# array_4x4.net
KiCad netlist of a schematic drawn in EAGLE
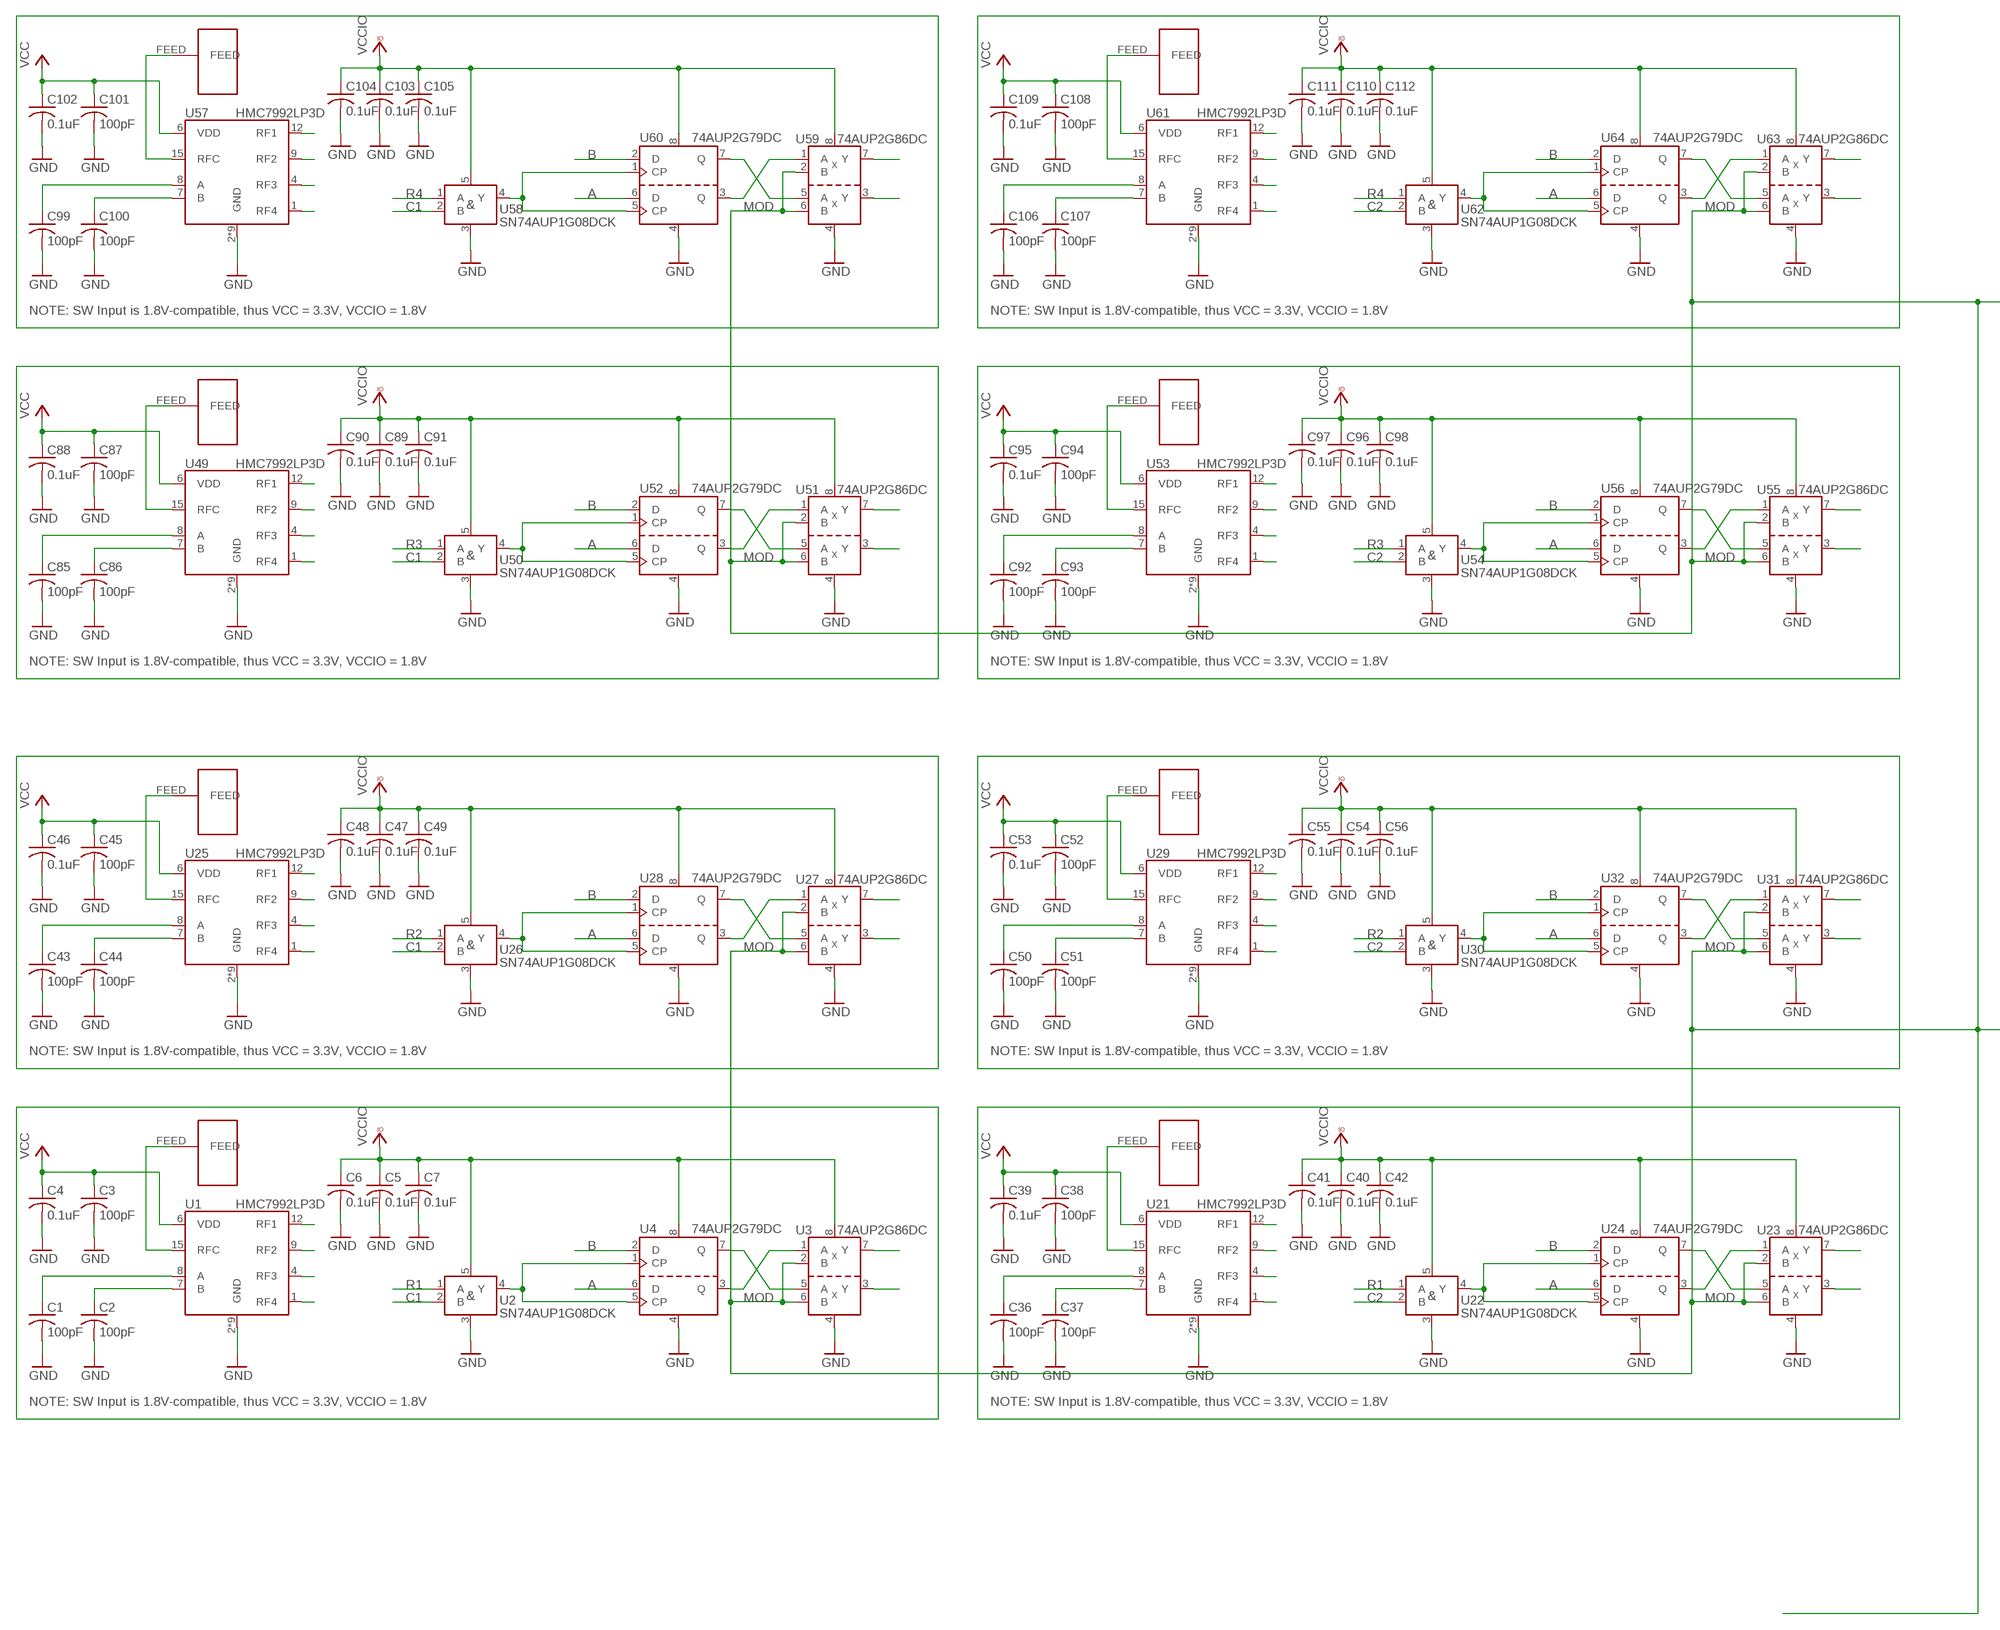
[diagram p0: schematic, sheet 1, part 1 of 2]
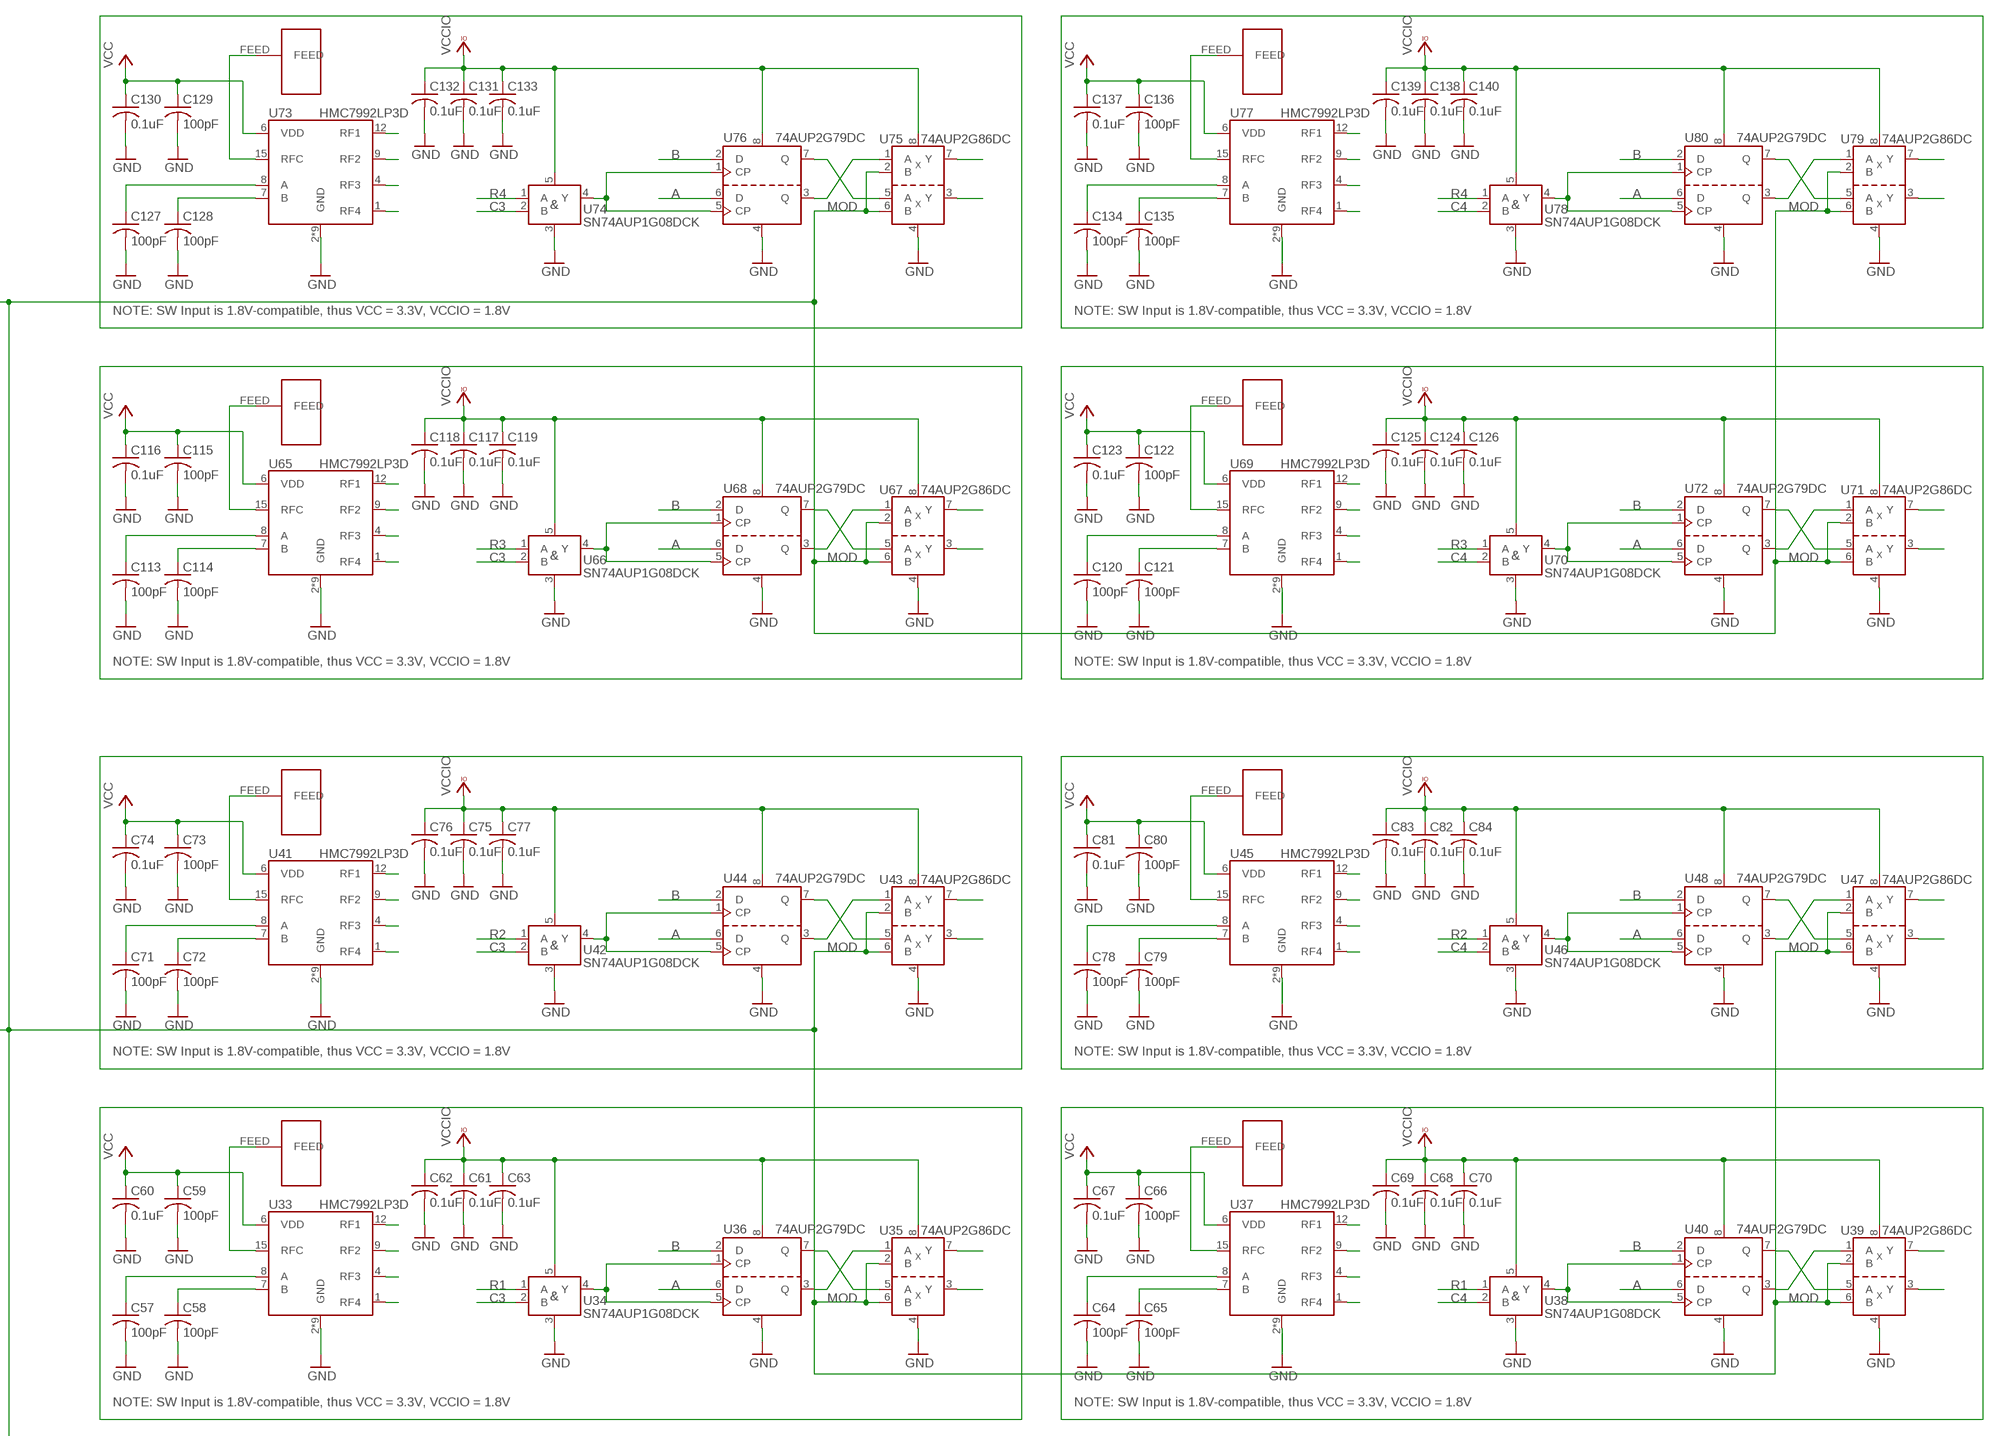
[diagram p1: schematic, sheet 1, part 2 of 2]

(export (version "E")
  (design (tool "Eeschema 10.0.6"))
  (components
    (comp (ref "ANT1")
      (value "5GANTENNA")
      (footprint "eagle-import:5GANTENNA")
      (libsource (lib "eagle-import") (part "5GANTENNA"))
    )
    (comp (ref "ANT6")
      (value "5GANTENNA")
      (footprint "eagle-import:5GANTENNA")
      (libsource (lib "eagle-import") (part "5GANTENNA"))
    )
    (comp (ref "ANT7")
      (value "5GANTENNA")
      (footprint "eagle-import:5GANTENNA")
      (libsource (lib "eagle-import") (part "5GANTENNA"))
    )
    (comp (ref "ANT8")
      (value "5GANTENNA")
      (footprint "eagle-import:5GANTENNA")
      (libsource (lib "eagle-import") (part "5GANTENNA"))
    )
    (comp (ref "ANT9")
      (value "5GANTENNA")
      (footprint "eagle-import:5GANTENNA")
      (libsource (lib "eagle-import") (part "5GANTENNA"))
    )
    (comp (ref "ANT10")
      (value "5GANTENNA")
      (footprint "eagle-import:5GANTENNA")
      (libsource (lib "eagle-import") (part "5GANTENNA"))
    )
    (comp (ref "ANT11")
      (value "5GANTENNA")
      (footprint "eagle-import:5GANTENNA")
      (libsource (lib "eagle-import") (part "5GANTENNA"))
    )
    (comp (ref "ANT12")
      (value "5GANTENNA")
      (footprint "eagle-import:5GANTENNA")
      (libsource (lib "eagle-import") (part "5GANTENNA"))
    )
    (comp (ref "ANT13")
      (value "5GANTENNA")
      (footprint "eagle-import:5GANTENNA")
      (libsource (lib "eagle-import") (part "5GANTENNA"))
    )
    (comp (ref "ANT14")
      (value "5GANTENNA")
      (footprint "eagle-import:5GANTENNA")
      (libsource (lib "eagle-import") (part "5GANTENNA"))
    )
    (comp (ref "ANT15")
      (value "5GANTENNA")
      (footprint "eagle-import:5GANTENNA")
      (libsource (lib "eagle-import") (part "5GANTENNA"))
    )
    (comp (ref "ANT16")
      (value "5GANTENNA")
      (footprint "eagle-import:5GANTENNA")
      (libsource (lib "eagle-import") (part "5GANTENNA"))
    )
    (comp (ref "ANT17")
      (value "5GANTENNA")
      (footprint "eagle-import:5GANTENNA")
      (libsource (lib "eagle-import") (part "5GANTENNA"))
    )
    (comp (ref "ANT18")
      (value "5GANTENNA")
      (footprint "eagle-import:5GANTENNA")
      (libsource (lib "eagle-import") (part "5GANTENNA"))
    )
    (comp (ref "ANT19")
      (value "5GANTENNA")
      (footprint "eagle-import:5GANTENNA")
      (libsource (lib "eagle-import") (part "5GANTENNA"))
    )
    (comp (ref "ANT20")
      (value "5GANTENNA")
      (footprint "eagle-import:5GANTENNA")
      (libsource (lib "eagle-import") (part "5GANTENNA"))
    )
    (comp (ref "C1")
      (value "100pF")
      (footprint "eagle-import:C0402")
      (libsource (lib "eagle-import") (part "C-USC0402"))
    )
    (comp (ref "C2")
      (value "100pF")
      (footprint "eagle-import:C0402")
      (libsource (lib "eagle-import") (part "C-USC0402"))
    )
    (comp (ref "C3")
      (value "100pF")
      (footprint "eagle-import:C0402")
      (libsource (lib "eagle-import") (part "C-USC0402"))
    )
    (comp (ref "C4")
      (value "0.1uF")
      (footprint "eagle-import:C0402")
      (libsource (lib "eagle-import") (part "C-USC0402"))
    )
    (comp (ref "C5")
      (value "0.1uF")
      (footprint "eagle-import:C0402")
      (libsource (lib "eagle-import") (part "C-USC0402"))
    )
    (comp (ref "C6")
      (value "0.1uF")
      (footprint "eagle-import:C0402")
      (libsource (lib "eagle-import") (part "C-USC0402"))
    )
    (comp (ref "C7")
      (value "0.1uF")
      (footprint "eagle-import:C0402")
      (libsource (lib "eagle-import") (part "C-USC0402"))
    )
    (comp (ref "C36")
      (value "100pF")
      (footprint "eagle-import:C0402")
      (libsource (lib "eagle-import") (part "C-USC0402"))
    )
    (comp (ref "C37")
      (value "100pF")
      (footprint "eagle-import:C0402")
      (libsource (lib "eagle-import") (part "C-USC0402"))
    )
    (comp (ref "C38")
      (value "100pF")
      (footprint "eagle-import:C0402")
      (libsource (lib "eagle-import") (part "C-USC0402"))
    )
    (comp (ref "C39")
      (value "0.1uF")
      (footprint "eagle-import:C0402")
      (libsource (lib "eagle-import") (part "C-USC0402"))
    )
    (comp (ref "C40")
      (value "0.1uF")
      (footprint "eagle-import:C0402")
      (libsource (lib "eagle-import") (part "C-USC0402"))
    )
    (comp (ref "C41")
      (value "0.1uF")
      (footprint "eagle-import:C0402")
      (libsource (lib "eagle-import") (part "C-USC0402"))
    )
    (comp (ref "C42")
      (value "0.1uF")
      (footprint "eagle-import:C0402")
      (libsource (lib "eagle-import") (part "C-USC0402"))
    )
    (comp (ref "C43")
      (value "100pF")
      (footprint "eagle-import:C0402")
      (libsource (lib "eagle-import") (part "C-USC0402"))
    )
    (comp (ref "C44")
      (value "100pF")
      (footprint "eagle-import:C0402")
      (libsource (lib "eagle-import") (part "C-USC0402"))
    )
    (comp (ref "C45")
      (value "100pF")
      (footprint "eagle-import:C0402")
      (libsource (lib "eagle-import") (part "C-USC0402"))
    )
    (comp (ref "C46")
      (value "0.1uF")
      (footprint "eagle-import:C0402")
      (libsource (lib "eagle-import") (part "C-USC0402"))
    )
    (comp (ref "C47")
      (value "0.1uF")
      (footprint "eagle-import:C0402")
      (libsource (lib "eagle-import") (part "C-USC0402"))
    )
    (comp (ref "C48")
      (value "0.1uF")
      (footprint "eagle-import:C0402")
      (libsource (lib "eagle-import") (part "C-USC0402"))
    )
    (comp (ref "C49")
      (value "0.1uF")
      (footprint "eagle-import:C0402")
      (libsource (lib "eagle-import") (part "C-USC0402"))
    )
    (comp (ref "C50")
      (value "100pF")
      (footprint "eagle-import:C0402")
      (libsource (lib "eagle-import") (part "C-USC0402"))
    )
    (comp (ref "C51")
      (value "100pF")
      (footprint "eagle-import:C0402")
      (libsource (lib "eagle-import") (part "C-USC0402"))
    )
    (comp (ref "C52")
      (value "100pF")
      (footprint "eagle-import:C0402")
      (libsource (lib "eagle-import") (part "C-USC0402"))
    )
    (comp (ref "C53")
      (value "0.1uF")
      (footprint "eagle-import:C0402")
      (libsource (lib "eagle-import") (part "C-USC0402"))
    )
    (comp (ref "C54")
      (value "0.1uF")
      (footprint "eagle-import:C0402")
      (libsource (lib "eagle-import") (part "C-USC0402"))
    )
    (comp (ref "C55")
      (value "0.1uF")
      (footprint "eagle-import:C0402")
      (libsource (lib "eagle-import") (part "C-USC0402"))
    )
    (comp (ref "C56")
      (value "0.1uF")
      (footprint "eagle-import:C0402")
      (libsource (lib "eagle-import") (part "C-USC0402"))
    )
    (comp (ref "C57")
      (value "100pF")
      (footprint "eagle-import:C0402")
      (libsource (lib "eagle-import") (part "C-USC0402"))
    )
    (comp (ref "C58")
      (value "100pF")
      (footprint "eagle-import:C0402")
      (libsource (lib "eagle-import") (part "C-USC0402"))
    )
    (comp (ref "C59")
      (value "100pF")
      (footprint "eagle-import:C0402")
      (libsource (lib "eagle-import") (part "C-USC0402"))
    )
    (comp (ref "C60")
      (value "0.1uF")
      (footprint "eagle-import:C0402")
      (libsource (lib "eagle-import") (part "C-USC0402"))
    )
    (comp (ref "C61")
      (value "0.1uF")
      (footprint "eagle-import:C0402")
      (libsource (lib "eagle-import") (part "C-USC0402"))
    )
    (comp (ref "C62")
      (value "0.1uF")
      (footprint "eagle-import:C0402")
      (libsource (lib "eagle-import") (part "C-USC0402"))
    )
    (comp (ref "C63")
      (value "0.1uF")
      (footprint "eagle-import:C0402")
      (libsource (lib "eagle-import") (part "C-USC0402"))
    )
    (comp (ref "C64")
      (value "100pF")
      (footprint "eagle-import:C0402")
      (libsource (lib "eagle-import") (part "C-USC0402"))
    )
    (comp (ref "C65")
      (value "100pF")
      (footprint "eagle-import:C0402")
      (libsource (lib "eagle-import") (part "C-USC0402"))
    )
    (comp (ref "C66")
      (value "100pF")
      (footprint "eagle-import:C0402")
      (libsource (lib "eagle-import") (part "C-USC0402"))
    )
    (comp (ref "C67")
      (value "0.1uF")
      (footprint "eagle-import:C0402")
      (libsource (lib "eagle-import") (part "C-USC0402"))
    )
    (comp (ref "C68")
      (value "0.1uF")
      (footprint "eagle-import:C0402")
      (libsource (lib "eagle-import") (part "C-USC0402"))
    )
    (comp (ref "C69")
      (value "0.1uF")
      (footprint "eagle-import:C0402")
      (libsource (lib "eagle-import") (part "C-USC0402"))
    )
    (comp (ref "C70")
      (value "0.1uF")
      (footprint "eagle-import:C0402")
      (libsource (lib "eagle-import") (part "C-USC0402"))
    )
    (comp (ref "C71")
      (value "100pF")
      (footprint "eagle-import:C0402")
      (libsource (lib "eagle-import") (part "C-USC0402"))
    )
    (comp (ref "C72")
      (value "100pF")
      (footprint "eagle-import:C0402")
      (libsource (lib "eagle-import") (part "C-USC0402"))
    )
    (comp (ref "C73")
      (value "100pF")
      (footprint "eagle-import:C0402")
      (libsource (lib "eagle-import") (part "C-USC0402"))
    )
    (comp (ref "C74")
      (value "0.1uF")
      (footprint "eagle-import:C0402")
      (libsource (lib "eagle-import") (part "C-USC0402"))
    )
    (comp (ref "C75")
      (value "0.1uF")
      (footprint "eagle-import:C0402")
      (libsource (lib "eagle-import") (part "C-USC0402"))
    )
    (comp (ref "C76")
      (value "0.1uF")
      (footprint "eagle-import:C0402")
      (libsource (lib "eagle-import") (part "C-USC0402"))
    )
    (comp (ref "C77")
      (value "0.1uF")
      (footprint "eagle-import:C0402")
      (libsource (lib "eagle-import") (part "C-USC0402"))
    )
    (comp (ref "C78")
      (value "100pF")
      (footprint "eagle-import:C0402")
      (libsource (lib "eagle-import") (part "C-USC0402"))
    )
    (comp (ref "C79")
      (value "100pF")
      (footprint "eagle-import:C0402")
      (libsource (lib "eagle-import") (part "C-USC0402"))
    )
    (comp (ref "C80")
      (value "100pF")
      (footprint "eagle-import:C0402")
      (libsource (lib "eagle-import") (part "C-USC0402"))
    )
    (comp (ref "C81")
      (value "0.1uF")
      (footprint "eagle-import:C0402")
      (libsource (lib "eagle-import") (part "C-USC0402"))
    )
    (comp (ref "C82")
      (value "0.1uF")
      (footprint "eagle-import:C0402")
      (libsource (lib "eagle-import") (part "C-USC0402"))
    )
    (comp (ref "C83")
      (value "0.1uF")
      (footprint "eagle-import:C0402")
      (libsource (lib "eagle-import") (part "C-USC0402"))
    )
    (comp (ref "C84")
      (value "0.1uF")
      (footprint "eagle-import:C0402")
      (libsource (lib "eagle-import") (part "C-USC0402"))
    )
    (comp (ref "C85")
      (value "100pF")
      (footprint "eagle-import:C0402")
      (libsource (lib "eagle-import") (part "C-USC0402"))
    )
    (comp (ref "C86")
      (value "100pF")
      (footprint "eagle-import:C0402")
      (libsource (lib "eagle-import") (part "C-USC0402"))
    )
    (comp (ref "C87")
      (value "100pF")
      (footprint "eagle-import:C0402")
      (libsource (lib "eagle-import") (part "C-USC0402"))
    )
    (comp (ref "C88")
      (value "0.1uF")
      (footprint "eagle-import:C0402")
      (libsource (lib "eagle-import") (part "C-USC0402"))
    )
    (comp (ref "C89")
      (value "0.1uF")
      (footprint "eagle-import:C0402")
      (libsource (lib "eagle-import") (part "C-USC0402"))
    )
    (comp (ref "C90")
      (value "0.1uF")
      (footprint "eagle-import:C0402")
      (libsource (lib "eagle-import") (part "C-USC0402"))
    )
    (comp (ref "C91")
      (value "0.1uF")
      (footprint "eagle-import:C0402")
      (libsource (lib "eagle-import") (part "C-USC0402"))
    )
    (comp (ref "C92")
      (value "100pF")
      (footprint "eagle-import:C0402")
      (libsource (lib "eagle-import") (part "C-USC0402"))
    )
    (comp (ref "C93")
      (value "100pF")
      (footprint "eagle-import:C0402")
      (libsource (lib "eagle-import") (part "C-USC0402"))
    )
    (comp (ref "C94")
      (value "100pF")
      (footprint "eagle-import:C0402")
      (libsource (lib "eagle-import") (part "C-USC0402"))
    )
    (comp (ref "C95")
      (value "0.1uF")
      (footprint "eagle-import:C0402")
      (libsource (lib "eagle-import") (part "C-USC0402"))
    )
    (comp (ref "C96")
      (value "0.1uF")
      (footprint "eagle-import:C0402")
      (libsource (lib "eagle-import") (part "C-USC0402"))
    )
    (comp (ref "C97")
      (value "0.1uF")
      (footprint "eagle-import:C0402")
      (libsource (lib "eagle-import") (part "C-USC0402"))
    )
    (comp (ref "C98")
      (value "0.1uF")
      (footprint "eagle-import:C0402")
      (libsource (lib "eagle-import") (part "C-USC0402"))
    )
    (comp (ref "C99")
      (value "100pF")
      (footprint "eagle-import:C0402")
      (libsource (lib "eagle-import") (part "C-USC0402"))
    )
    (comp (ref "C100")
      (value "100pF")
      (footprint "eagle-import:C0402")
      (libsource (lib "eagle-import") (part "C-USC0402"))
    )
    (comp (ref "C101")
      (value "100pF")
      (footprint "eagle-import:C0402")
      (libsource (lib "eagle-import") (part "C-USC0402"))
    )
    (comp (ref "C102")
      (value "0.1uF")
      (footprint "eagle-import:C0402")
      (libsource (lib "eagle-import") (part "C-USC0402"))
    )
    (comp (ref "C103")
      (value "0.1uF")
      (footprint "eagle-import:C0402")
      (libsource (lib "eagle-import") (part "C-USC0402"))
    )
    (comp (ref "C104")
      (value "0.1uF")
      (footprint "eagle-import:C0402")
      (libsource (lib "eagle-import") (part "C-USC0402"))
    )
    (comp (ref "C105")
      (value "0.1uF")
      (footprint "eagle-import:C0402")
      (libsource (lib "eagle-import") (part "C-USC0402"))
    )
    (comp (ref "C106")
      (value "100pF")
      (footprint "eagle-import:C0402")
      (libsource (lib "eagle-import") (part "C-USC0402"))
    )
    (comp (ref "C107")
      (value "100pF")
      (footprint "eagle-import:C0402")
      (libsource (lib "eagle-import") (part "C-USC0402"))
    )
    (comp (ref "C108")
      (value "100pF")
      (footprint "eagle-import:C0402")
      (libsource (lib "eagle-import") (part "C-USC0402"))
    )
    (comp (ref "C109")
      (value "0.1uF")
      (footprint "eagle-import:C0402")
      (libsource (lib "eagle-import") (part "C-USC0402"))
    )
    (comp (ref "C110")
      (value "0.1uF")
      (footprint "eagle-import:C0402")
      (libsource (lib "eagle-import") (part "C-USC0402"))
    )
    (comp (ref "C111")
      (value "0.1uF")
      (footprint "eagle-import:C0402")
      (libsource (lib "eagle-import") (part "C-USC0402"))
    )
    (comp (ref "C112")
      (value "0.1uF")
      (footprint "eagle-import:C0402")
      (libsource (lib "eagle-import") (part "C-USC0402"))
    )
    (comp (ref "C113")
      (value "100pF")
      (footprint "eagle-import:C0402")
      (libsource (lib "eagle-import") (part "C-USC0402"))
    )
    (comp (ref "C114")
      (value "100pF")
      (footprint "eagle-import:C0402")
      (libsource (lib "eagle-import") (part "C-USC0402"))
    )
    (comp (ref "C115")
      (value "100pF")
      (footprint "eagle-import:C0402")
      (libsource (lib "eagle-import") (part "C-USC0402"))
    )
    (comp (ref "C116")
      (value "0.1uF")
      (footprint "eagle-import:C0402")
      (libsource (lib "eagle-import") (part "C-USC0402"))
    )
    (comp (ref "C117")
      (value "0.1uF")
      (footprint "eagle-import:C0402")
      (libsource (lib "eagle-import") (part "C-USC0402"))
    )
    (comp (ref "C118")
      (value "0.1uF")
      (footprint "eagle-import:C0402")
      (libsource (lib "eagle-import") (part "C-USC0402"))
    )
    (comp (ref "C119")
      (value "0.1uF")
      (footprint "eagle-import:C0402")
      (libsource (lib "eagle-import") (part "C-USC0402"))
    )
    (comp (ref "C120")
      (value "100pF")
      (footprint "eagle-import:C0402")
      (libsource (lib "eagle-import") (part "C-USC0402"))
    )
    (comp (ref "C121")
      (value "100pF")
      (footprint "eagle-import:C0402")
      (libsource (lib "eagle-import") (part "C-USC0402"))
    )
    (comp (ref "C122")
      (value "100pF")
      (footprint "eagle-import:C0402")
      (libsource (lib "eagle-import") (part "C-USC0402"))
    )
    (comp (ref "C123")
      (value "0.1uF")
      (footprint "eagle-import:C0402")
      (libsource (lib "eagle-import") (part "C-USC0402"))
    )
    (comp (ref "C124")
      (value "0.1uF")
      (footprint "eagle-import:C0402")
      (libsource (lib "eagle-import") (part "C-USC0402"))
    )
    (comp (ref "C125")
      (value "0.1uF")
      (footprint "eagle-import:C0402")
      (libsource (lib "eagle-import") (part "C-USC0402"))
    )
    (comp (ref "C126")
      (value "0.1uF")
      (footprint "eagle-import:C0402")
      (libsource (lib "eagle-import") (part "C-USC0402"))
    )
    (comp (ref "C127")
      (value "100pF")
      (footprint "eagle-import:C0402")
      (libsource (lib "eagle-import") (part "C-USC0402"))
    )
    (comp (ref "C128")
      (value "100pF")
      (footprint "eagle-import:C0402")
      (libsource (lib "eagle-import") (part "C-USC0402"))
    )
    (comp (ref "C129")
      (value "100pF")
      (footprint "eagle-import:C0402")
      (libsource (lib "eagle-import") (part "C-USC0402"))
    )
    (comp (ref "C130")
      (value "0.1uF")
      (footprint "eagle-import:C0402")
      (libsource (lib "eagle-import") (part "C-USC0402"))
    )
    (comp (ref "C131")
      (value "0.1uF")
      (footprint "eagle-import:C0402")
      (libsource (lib "eagle-import") (part "C-USC0402"))
    )
    (comp (ref "C132")
      (value "0.1uF")
      (footprint "eagle-import:C0402")
      (libsource (lib "eagle-import") (part "C-USC0402"))
    )
    (comp (ref "C133")
      (value "0.1uF")
      (footprint "eagle-import:C0402")
      (libsource (lib "eagle-import") (part "C-USC0402"))
    )
    (comp (ref "C134")
      (value "100pF")
      (footprint "eagle-import:C0402")
      (libsource (lib "eagle-import") (part "C-USC0402"))
    )
    (comp (ref "C135")
      (value "100pF")
      (footprint "eagle-import:C0402")
      (libsource (lib "eagle-import") (part "C-USC0402"))
    )
    (comp (ref "C136")
      (value "100pF")
      (footprint "eagle-import:C0402")
      (libsource (lib "eagle-import") (part "C-USC0402"))
    )
    (comp (ref "C137")
      (value "0.1uF")
      (footprint "eagle-import:C0402")
      (libsource (lib "eagle-import") (part "C-USC0402"))
    )
    (comp (ref "C138")
      (value "0.1uF")
      (footprint "eagle-import:C0402")
      (libsource (lib "eagle-import") (part "C-USC0402"))
    )
    (comp (ref "C139")
      (value "0.1uF")
      (footprint "eagle-import:C0402")
      (libsource (lib "eagle-import") (part "C-USC0402"))
    )
    (comp (ref "C140")
      (value "0.1uF")
      (footprint "eagle-import:C0402")
      (libsource (lib "eagle-import") (part "C-USC0402"))
    )
    (comp (ref "U1")
      (value "HMC7992LP3D")
      (footprint "eagle-import:QFN-16-3X3")
      (libsource (lib "eagle-import") (part "HMC7992LP3D"))
    )
    (comp (ref "U2")
      (value "SN74AUP1G08DCK")
      (footprint "eagle-import:SOT-353")
      (libsource (lib "eagle-import") (part "SN74AUP1G08DCK"))
    )
    (comp (ref "U3")
      (value "74AUP2G86DC")
      (footprint "eagle-import:VSSOP-8")
      (libsource (lib "eagle-import") (part "74AUP2G86DC"))
    )
    (comp (ref "U4")
      (value "74AUP2G79DC")
      (footprint "eagle-import:VSSOP-8")
      (libsource (lib "eagle-import") (part "74AUP2G79DC"))
    )
    (comp (ref "U21")
      (value "HMC7992LP3D")
      (footprint "eagle-import:QFN-16-3X3")
      (libsource (lib "eagle-import") (part "HMC7992LP3D"))
    )
    (comp (ref "U22")
      (value "SN74AUP1G08DCK")
      (footprint "eagle-import:SOT-353")
      (libsource (lib "eagle-import") (part "SN74AUP1G08DCK"))
    )
    (comp (ref "U23")
      (value "74AUP2G86DC")
      (footprint "eagle-import:VSSOP-8")
      (libsource (lib "eagle-import") (part "74AUP2G86DC"))
    )
    (comp (ref "U24")
      (value "74AUP2G79DC")
      (footprint "eagle-import:VSSOP-8")
      (libsource (lib "eagle-import") (part "74AUP2G79DC"))
    )
    (comp (ref "U25")
      (value "HMC7992LP3D")
      (footprint "eagle-import:QFN-16-3X3")
      (libsource (lib "eagle-import") (part "HMC7992LP3D"))
    )
    (comp (ref "U26")
      (value "SN74AUP1G08DCK")
      (footprint "eagle-import:SOT-353")
      (libsource (lib "eagle-import") (part "SN74AUP1G08DCK"))
    )
    (comp (ref "U27")
      (value "74AUP2G86DC")
      (footprint "eagle-import:VSSOP-8")
      (libsource (lib "eagle-import") (part "74AUP2G86DC"))
    )
    (comp (ref "U28")
      (value "74AUP2G79DC")
      (footprint "eagle-import:VSSOP-8")
      (libsource (lib "eagle-import") (part "74AUP2G79DC"))
    )
    (comp (ref "U29")
      (value "HMC7992LP3D")
      (footprint "eagle-import:QFN-16-3X3")
      (libsource (lib "eagle-import") (part "HMC7992LP3D"))
    )
    (comp (ref "U30")
      (value "SN74AUP1G08DCK")
      (footprint "eagle-import:SOT-353")
      (libsource (lib "eagle-import") (part "SN74AUP1G08DCK"))
    )
    (comp (ref "U31")
      (value "74AUP2G86DC")
      (footprint "eagle-import:VSSOP-8")
      (libsource (lib "eagle-import") (part "74AUP2G86DC"))
    )
    (comp (ref "U32")
      (value "74AUP2G79DC")
      (footprint "eagle-import:VSSOP-8")
      (libsource (lib "eagle-import") (part "74AUP2G79DC"))
    )
    (comp (ref "U33")
      (value "HMC7992LP3D")
      (footprint "eagle-import:QFN-16-3X3")
      (libsource (lib "eagle-import") (part "HMC7992LP3D"))
    )
    (comp (ref "U34")
      (value "SN74AUP1G08DCK")
      (footprint "eagle-import:SOT-353")
      (libsource (lib "eagle-import") (part "SN74AUP1G08DCK"))
    )
    (comp (ref "U35")
      (value "74AUP2G86DC")
      (footprint "eagle-import:VSSOP-8")
      (libsource (lib "eagle-import") (part "74AUP2G86DC"))
    )
    (comp (ref "U36")
      (value "74AUP2G79DC")
      (footprint "eagle-import:VSSOP-8")
      (libsource (lib "eagle-import") (part "74AUP2G79DC"))
    )
    (comp (ref "U37")
      (value "HMC7992LP3D")
      (footprint "eagle-import:QFN-16-3X3")
      (libsource (lib "eagle-import") (part "HMC7992LP3D"))
    )
    (comp (ref "U38")
      (value "SN74AUP1G08DCK")
      (footprint "eagle-import:SOT-353")
      (libsource (lib "eagle-import") (part "SN74AUP1G08DCK"))
    )
    (comp (ref "U39")
      (value "74AUP2G86DC")
      (footprint "eagle-import:VSSOP-8")
      (libsource (lib "eagle-import") (part "74AUP2G86DC"))
    )
    (comp (ref "U40")
      (value "74AUP2G79DC")
      (footprint "eagle-import:VSSOP-8")
      (libsource (lib "eagle-import") (part "74AUP2G79DC"))
    )
    (comp (ref "U41")
      (value "HMC7992LP3D")
      (footprint "eagle-import:QFN-16-3X3")
      (libsource (lib "eagle-import") (part "HMC7992LP3D"))
    )
    (comp (ref "U42")
      (value "SN74AUP1G08DCK")
      (footprint "eagle-import:SOT-353")
      (libsource (lib "eagle-import") (part "SN74AUP1G08DCK"))
    )
    (comp (ref "U43")
      (value "74AUP2G86DC")
      (footprint "eagle-import:VSSOP-8")
      (libsource (lib "eagle-import") (part "74AUP2G86DC"))
    )
    (comp (ref "U44")
      (value "74AUP2G79DC")
      (footprint "eagle-import:VSSOP-8")
      (libsource (lib "eagle-import") (part "74AUP2G79DC"))
    )
    (comp (ref "U45")
      (value "HMC7992LP3D")
      (footprint "eagle-import:QFN-16-3X3")
      (libsource (lib "eagle-import") (part "HMC7992LP3D"))
    )
    (comp (ref "U46")
      (value "SN74AUP1G08DCK")
      (footprint "eagle-import:SOT-353")
      (libsource (lib "eagle-import") (part "SN74AUP1G08DCK"))
    )
    (comp (ref "U47")
      (value "74AUP2G86DC")
      (footprint "eagle-import:VSSOP-8")
      (libsource (lib "eagle-import") (part "74AUP2G86DC"))
    )
    (comp (ref "U48")
      (value "74AUP2G79DC")
      (footprint "eagle-import:VSSOP-8")
      (libsource (lib "eagle-import") (part "74AUP2G79DC"))
    )
    (comp (ref "U49")
      (value "HMC7992LP3D")
      (footprint "eagle-import:QFN-16-3X3")
      (libsource (lib "eagle-import") (part "HMC7992LP3D"))
    )
    (comp (ref "U50")
      (value "SN74AUP1G08DCK")
      (footprint "eagle-import:SOT-353")
      (libsource (lib "eagle-import") (part "SN74AUP1G08DCK"))
    )
    (comp (ref "U51")
      (value "74AUP2G86DC")
      (footprint "eagle-import:VSSOP-8")
      (libsource (lib "eagle-import") (part "74AUP2G86DC"))
    )
    (comp (ref "U52")
      (value "74AUP2G79DC")
      (footprint "eagle-import:VSSOP-8")
      (libsource (lib "eagle-import") (part "74AUP2G79DC"))
    )
    (comp (ref "U53")
      (value "HMC7992LP3D")
      (footprint "eagle-import:QFN-16-3X3")
      (libsource (lib "eagle-import") (part "HMC7992LP3D"))
    )
    (comp (ref "U54")
      (value "SN74AUP1G08DCK")
      (footprint "eagle-import:SOT-353")
      (libsource (lib "eagle-import") (part "SN74AUP1G08DCK"))
    )
    (comp (ref "U55")
      (value "74AUP2G86DC")
      (footprint "eagle-import:VSSOP-8")
      (libsource (lib "eagle-import") (part "74AUP2G86DC"))
    )
    (comp (ref "U56")
      (value "74AUP2G79DC")
      (footprint "eagle-import:VSSOP-8")
      (libsource (lib "eagle-import") (part "74AUP2G79DC"))
    )
    (comp (ref "U57")
      (value "HMC7992LP3D")
      (footprint "eagle-import:QFN-16-3X3")
      (libsource (lib "eagle-import") (part "HMC7992LP3D"))
    )
    (comp (ref "U58")
      (value "SN74AUP1G08DCK")
      (footprint "eagle-import:SOT-353")
      (libsource (lib "eagle-import") (part "SN74AUP1G08DCK"))
    )
    (comp (ref "U59")
      (value "74AUP2G86DC")
      (footprint "eagle-import:VSSOP-8")
      (libsource (lib "eagle-import") (part "74AUP2G86DC"))
    )
    (comp (ref "U60")
      (value "74AUP2G79DC")
      (footprint "eagle-import:VSSOP-8")
      (libsource (lib "eagle-import") (part "74AUP2G79DC"))
    )
    (comp (ref "U61")
      (value "HMC7992LP3D")
      (footprint "eagle-import:QFN-16-3X3")
      (libsource (lib "eagle-import") (part "HMC7992LP3D"))
    )
    (comp (ref "U62")
      (value "SN74AUP1G08DCK")
      (footprint "eagle-import:SOT-353")
      (libsource (lib "eagle-import") (part "SN74AUP1G08DCK"))
    )
    (comp (ref "U63")
      (value "74AUP2G86DC")
      (footprint "eagle-import:VSSOP-8")
      (libsource (lib "eagle-import") (part "74AUP2G86DC"))
    )
    (comp (ref "U64")
      (value "74AUP2G79DC")
      (footprint "eagle-import:VSSOP-8")
      (libsource (lib "eagle-import") (part "74AUP2G79DC"))
    )
    (comp (ref "U65")
      (value "HMC7992LP3D")
      (footprint "eagle-import:QFN-16-3X3")
      (libsource (lib "eagle-import") (part "HMC7992LP3D"))
    )
    (comp (ref "U66")
      (value "SN74AUP1G08DCK")
      (footprint "eagle-import:SOT-353")
      (libsource (lib "eagle-import") (part "SN74AUP1G08DCK"))
    )
    (comp (ref "U67")
      (value "74AUP2G86DC")
      (footprint "eagle-import:VSSOP-8")
      (libsource (lib "eagle-import") (part "74AUP2G86DC"))
    )
    (comp (ref "U68")
      (value "74AUP2G79DC")
      (footprint "eagle-import:VSSOP-8")
      (libsource (lib "eagle-import") (part "74AUP2G79DC"))
    )
    (comp (ref "U69")
      (value "HMC7992LP3D")
      (footprint "eagle-import:QFN-16-3X3")
      (libsource (lib "eagle-import") (part "HMC7992LP3D"))
    )
    (comp (ref "U70")
      (value "SN74AUP1G08DCK")
      (footprint "eagle-import:SOT-353")
      (libsource (lib "eagle-import") (part "SN74AUP1G08DCK"))
    )
    (comp (ref "U71")
      (value "74AUP2G86DC")
      (footprint "eagle-import:VSSOP-8")
      (libsource (lib "eagle-import") (part "74AUP2G86DC"))
    )
    (comp (ref "U72")
      (value "74AUP2G79DC")
      (footprint "eagle-import:VSSOP-8")
      (libsource (lib "eagle-import") (part "74AUP2G79DC"))
    )
    (comp (ref "U73")
      (value "HMC7992LP3D")
      (footprint "eagle-import:QFN-16-3X3")
      (libsource (lib "eagle-import") (part "HMC7992LP3D"))
    )
    (comp (ref "U74")
      (value "SN74AUP1G08DCK")
      (footprint "eagle-import:SOT-353")
      (libsource (lib "eagle-import") (part "SN74AUP1G08DCK"))
    )
    (comp (ref "U75")
      (value "74AUP2G86DC")
      (footprint "eagle-import:VSSOP-8")
      (libsource (lib "eagle-import") (part "74AUP2G86DC"))
    )
    (comp (ref "U76")
      (value "74AUP2G79DC")
      (footprint "eagle-import:VSSOP-8")
      (libsource (lib "eagle-import") (part "74AUP2G79DC"))
    )
    (comp (ref "U77")
      (value "HMC7992LP3D")
      (footprint "eagle-import:QFN-16-3X3")
      (libsource (lib "eagle-import") (part "HMC7992LP3D"))
    )
    (comp (ref "U78")
      (value "SN74AUP1G08DCK")
      (footprint "eagle-import:SOT-353")
      (libsource (lib "eagle-import") (part "SN74AUP1G08DCK"))
    )
    (comp (ref "U79")
      (value "74AUP2G86DC")
      (footprint "eagle-import:VSSOP-8")
      (libsource (lib "eagle-import") (part "74AUP2G86DC"))
    )
    (comp (ref "U80")
      (value "74AUP2G79DC")
      (footprint "eagle-import:VSSOP-8")
      (libsource (lib "eagle-import") (part "74AUP2G79DC"))
    )
  )
  (nets
    (net (code "1") (name "/A") (class "Default")
      (node (ref "U24") (pin "6") (pinfunction "D_6") (pintype "input"))
      (node (ref "U28") (pin "6") (pinfunction "D_6") (pintype "input"))
      (node (ref "U32") (pin "6") (pinfunction "D_6") (pintype "input"))
      (node (ref "U36") (pin "6") (pinfunction "D_6") (pintype "input"))
      (node (ref "U4") (pin "6") (pinfunction "D_6") (pintype "input"))
      (node (ref "U40") (pin "6") (pinfunction "D_6") (pintype "input"))
      (node (ref "U44") (pin "6") (pinfunction "D_6") (pintype "input"))
      (node (ref "U48") (pin "6") (pinfunction "D_6") (pintype "input"))
      (node (ref "U52") (pin "6") (pinfunction "D_6") (pintype "input"))
      (node (ref "U56") (pin "6") (pinfunction "D_6") (pintype "input"))
      (node (ref "U60") (pin "6") (pinfunction "D_6") (pintype "input"))
      (node (ref "U64") (pin "6") (pinfunction "D_6") (pintype "input"))
      (node (ref "U68") (pin "6") (pinfunction "D_6") (pintype "input"))
      (node (ref "U72") (pin "6") (pinfunction "D_6") (pintype "input"))
      (node (ref "U76") (pin "6") (pinfunction "D_6") (pintype "input"))
      (node (ref "U80") (pin "6") (pinfunction "D_6") (pintype "input"))
    )
    (net (code "2") (name "/B") (class "Default")
      (node (ref "U24") (pin "2") (pinfunction "D_2") (pintype "input"))
      (node (ref "U28") (pin "2") (pinfunction "D_2") (pintype "input"))
      (node (ref "U32") (pin "2") (pinfunction "D_2") (pintype "input"))
      (node (ref "U36") (pin "2") (pinfunction "D_2") (pintype "input"))
      (node (ref "U4") (pin "2") (pinfunction "D_2") (pintype "input"))
      (node (ref "U40") (pin "2") (pinfunction "D_2") (pintype "input"))
      (node (ref "U44") (pin "2") (pinfunction "D_2") (pintype "input"))
      (node (ref "U48") (pin "2") (pinfunction "D_2") (pintype "input"))
      (node (ref "U52") (pin "2") (pinfunction "D_2") (pintype "input"))
      (node (ref "U56") (pin "2") (pinfunction "D_2") (pintype "input"))
      (node (ref "U60") (pin "2") (pinfunction "D_2") (pintype "input"))
      (node (ref "U64") (pin "2") (pinfunction "D_2") (pintype "input"))
      (node (ref "U68") (pin "2") (pinfunction "D_2") (pintype "input"))
      (node (ref "U72") (pin "2") (pinfunction "D_2") (pintype "input"))
      (node (ref "U76") (pin "2") (pinfunction "D_2") (pintype "input"))
      (node (ref "U80") (pin "2") (pinfunction "D_2") (pintype "input"))
    )
    (net (code "3") (name "/C1") (class "Default")
      (node (ref "U2") (pin "2") (pinfunction "B_2") (pintype "input"))
      (node (ref "U26") (pin "2") (pinfunction "B_2") (pintype "input"))
      (node (ref "U50") (pin "2") (pinfunction "B_2") (pintype "input"))
      (node (ref "U58") (pin "2") (pinfunction "B_2") (pintype "input"))
    )
    (net (code "4") (name "/C2") (class "Default")
      (node (ref "U22") (pin "2") (pinfunction "B_2") (pintype "input"))
      (node (ref "U30") (pin "2") (pinfunction "B_2") (pintype "input"))
      (node (ref "U54") (pin "2") (pinfunction "B_2") (pintype "input"))
      (node (ref "U62") (pin "2") (pinfunction "B_2") (pintype "input"))
    )
    (net (code "5") (name "/C3") (class "Default")
      (node (ref "U34") (pin "2") (pinfunction "B_2") (pintype "input"))
      (node (ref "U42") (pin "2") (pinfunction "B_2") (pintype "input"))
      (node (ref "U66") (pin "2") (pinfunction "B_2") (pintype "input"))
      (node (ref "U74") (pin "2") (pinfunction "B_2") (pintype "input"))
    )
    (net (code "6") (name "/C4") (class "Default")
      (node (ref "U38") (pin "2") (pinfunction "B_2") (pintype "input"))
      (node (ref "U46") (pin "2") (pinfunction "B_2") (pintype "input"))
      (node (ref "U70") (pin "2") (pinfunction "B_2") (pintype "input"))
      (node (ref "U78") (pin "2") (pinfunction "B_2") (pintype "input"))
    )
    (net (code "7") (name "/MOD") (class "Default")
      (node (ref "U23") (pin "2") (pinfunction "B_2") (pintype "input"))
      (node (ref "U23") (pin "6") (pinfunction "B_6") (pintype "input"))
      (node (ref "U27") (pin "2") (pinfunction "B_2") (pintype "input"))
      (node (ref "U27") (pin "6") (pinfunction "B_6") (pintype "input"))
      (node (ref "U3") (pin "2") (pinfunction "B_2") (pintype "input"))
      (node (ref "U3") (pin "6") (pinfunction "B_6") (pintype "input"))
      (node (ref "U31") (pin "2") (pinfunction "B_2") (pintype "input"))
      (node (ref "U31") (pin "6") (pinfunction "B_6") (pintype "input"))
      (node (ref "U35") (pin "2") (pinfunction "B_2") (pintype "input"))
      (node (ref "U35") (pin "6") (pinfunction "B_6") (pintype "input"))
      (node (ref "U39") (pin "2") (pinfunction "B_2") (pintype "input"))
      (node (ref "U39") (pin "6") (pinfunction "B_6") (pintype "input"))
      (node (ref "U43") (pin "2") (pinfunction "B_2") (pintype "input"))
      (node (ref "U43") (pin "6") (pinfunction "B_6") (pintype "input"))
      (node (ref "U47") (pin "2") (pinfunction "B_2") (pintype "input"))
      (node (ref "U47") (pin "6") (pinfunction "B_6") (pintype "input"))
      (node (ref "U51") (pin "2") (pinfunction "B_2") (pintype "input"))
      (node (ref "U51") (pin "6") (pinfunction "B_6") (pintype "input"))
      (node (ref "U55") (pin "2") (pinfunction "B_2") (pintype "input"))
      (node (ref "U55") (pin "6") (pinfunction "B_6") (pintype "input"))
      (node (ref "U59") (pin "2") (pinfunction "B_2") (pintype "input"))
      (node (ref "U59") (pin "6") (pinfunction "B_6") (pintype "input"))
      (node (ref "U63") (pin "2") (pinfunction "B_2") (pintype "input"))
      (node (ref "U63") (pin "6") (pinfunction "B_6") (pintype "input"))
      (node (ref "U67") (pin "2") (pinfunction "B_2") (pintype "input"))
      (node (ref "U67") (pin "6") (pinfunction "B_6") (pintype "input"))
      (node (ref "U71") (pin "2") (pinfunction "B_2") (pintype "input"))
      (node (ref "U71") (pin "6") (pinfunction "B_6") (pintype "input"))
      (node (ref "U75") (pin "2") (pinfunction "B_2") (pintype "input"))
      (node (ref "U75") (pin "6") (pinfunction "B_6") (pintype "input"))
      (node (ref "U79") (pin "2") (pinfunction "B_2") (pintype "input"))
      (node (ref "U79") (pin "6") (pinfunction "B_6") (pintype "input"))
    )
    (net (code "8") (name "/R1") (class "Default")
      (node (ref "U2") (pin "1") (pinfunction "A_1") (pintype "input"))
      (node (ref "U22") (pin "1") (pinfunction "A_1") (pintype "input"))
      (node (ref "U34") (pin "1") (pinfunction "A_1") (pintype "input"))
      (node (ref "U38") (pin "1") (pinfunction "A_1") (pintype "input"))
    )
    (net (code "9") (name "/R2") (class "Default")
      (node (ref "U26") (pin "1") (pinfunction "A_1") (pintype "input"))
      (node (ref "U30") (pin "1") (pinfunction "A_1") (pintype "input"))
      (node (ref "U42") (pin "1") (pinfunction "A_1") (pintype "input"))
      (node (ref "U46") (pin "1") (pinfunction "A_1") (pintype "input"))
    )
    (net (code "10") (name "/R3") (class "Default")
      (node (ref "U50") (pin "1") (pinfunction "A_1") (pintype "input"))
      (node (ref "U54") (pin "1") (pinfunction "A_1") (pintype "input"))
      (node (ref "U66") (pin "1") (pinfunction "A_1") (pintype "input"))
      (node (ref "U70") (pin "1") (pinfunction "A_1") (pintype "input"))
    )
    (net (code "11") (name "/R4") (class "Default")
      (node (ref "U58") (pin "1") (pinfunction "A_1") (pintype "input"))
      (node (ref "U62") (pin "1") (pinfunction "A_1") (pintype "input"))
      (node (ref "U74") (pin "1") (pinfunction "A_1") (pintype "input"))
      (node (ref "U78") (pin "1") (pinfunction "A_1") (pintype "input"))
    )
    (net (code "12") (name "/_AMOD_5") (class "Default")
      (node (ref "C1") (pin "1") (pinfunction "1_1") (pintype "passive"))
      (node (ref "U1") (pin "8") (pinfunction "A_8") (pintype "input"))
      (node (ref "U3") (pin "7") (pinfunction "Y_7") (pintype "output"))
    )
    (net (code "13") (name "/_AMOD_6") (class "Default")
      (node (ref "C36") (pin "1") (pinfunction "1_1") (pintype "passive"))
      (node (ref "U21") (pin "8") (pinfunction "A_8") (pintype "input"))
      (node (ref "U23") (pin "7") (pinfunction "Y_7") (pintype "output"))
    )
    (net (code "14") (name "/_AMOD_7") (class "Default")
      (node (ref "C43") (pin "1") (pinfunction "1_1") (pintype "passive"))
      (node (ref "U25") (pin "8") (pinfunction "A_8") (pintype "input"))
      (node (ref "U27") (pin "7") (pinfunction "Y_7") (pintype "output"))
    )
    (net (code "15") (name "/_AMOD_8") (class "Default")
      (node (ref "C50") (pin "1") (pinfunction "1_1") (pintype "passive"))
      (node (ref "U29") (pin "8") (pinfunction "A_8") (pintype "input"))
      (node (ref "U31") (pin "7") (pinfunction "Y_7") (pintype "output"))
    )
    (net (code "16") (name "/_AMOD_9") (class "Default")
      (node (ref "C57") (pin "1") (pinfunction "1_1") (pintype "passive"))
      (node (ref "U33") (pin "8") (pinfunction "A_8") (pintype "input"))
      (node (ref "U35") (pin "7") (pinfunction "Y_7") (pintype "output"))
    )
    (net (code "17") (name "/_AMOD_10") (class "Default")
      (node (ref "C64") (pin "1") (pinfunction "1_1") (pintype "passive"))
      (node (ref "U37") (pin "8") (pinfunction "A_8") (pintype "input"))
      (node (ref "U39") (pin "7") (pinfunction "Y_7") (pintype "output"))
    )
    (net (code "18") (name "/_AMOD_11") (class "Default")
      (node (ref "C71") (pin "1") (pinfunction "1_1") (pintype "passive"))
      (node (ref "U41") (pin "8") (pinfunction "A_8") (pintype "input"))
      (node (ref "U43") (pin "7") (pinfunction "Y_7") (pintype "output"))
    )
    (net (code "19") (name "/_AMOD_12") (class "Default")
      (node (ref "C78") (pin "1") (pinfunction "1_1") (pintype "passive"))
      (node (ref "U45") (pin "8") (pinfunction "A_8") (pintype "input"))
      (node (ref "U47") (pin "7") (pinfunction "Y_7") (pintype "output"))
    )
    (net (code "20") (name "/_AMOD_13") (class "Default")
      (node (ref "C85") (pin "1") (pinfunction "1_1") (pintype "passive"))
      (node (ref "U49") (pin "8") (pinfunction "A_8") (pintype "input"))
      (node (ref "U51") (pin "7") (pinfunction "Y_7") (pintype "output"))
    )
    (net (code "21") (name "/_AMOD_14") (class "Default")
      (node (ref "C92") (pin "1") (pinfunction "1_1") (pintype "passive"))
      (node (ref "U53") (pin "8") (pinfunction "A_8") (pintype "input"))
      (node (ref "U55") (pin "7") (pinfunction "Y_7") (pintype "output"))
    )
    (net (code "22") (name "/_AMOD_15") (class "Default")
      (node (ref "C99") (pin "1") (pinfunction "1_1") (pintype "passive"))
      (node (ref "U57") (pin "8") (pinfunction "A_8") (pintype "input"))
      (node (ref "U59") (pin "7") (pinfunction "Y_7") (pintype "output"))
    )
    (net (code "23") (name "/_AMOD_16") (class "Default")
      (node (ref "C106") (pin "1") (pinfunction "1_1") (pintype "passive"))
      (node (ref "U61") (pin "8") (pinfunction "A_8") (pintype "input"))
      (node (ref "U63") (pin "7") (pinfunction "Y_7") (pintype "output"))
    )
    (net (code "24") (name "/_AMOD_17") (class "Default")
      (node (ref "C113") (pin "1") (pinfunction "1_1") (pintype "passive"))
      (node (ref "U65") (pin "8") (pinfunction "A_8") (pintype "input"))
      (node (ref "U67") (pin "7") (pinfunction "Y_7") (pintype "output"))
    )
    (net (code "25") (name "/_AMOD_18") (class "Default")
      (node (ref "C120") (pin "1") (pinfunction "1_1") (pintype "passive"))
      (node (ref "U69") (pin "8") (pinfunction "A_8") (pintype "input"))
      (node (ref "U71") (pin "7") (pinfunction "Y_7") (pintype "output"))
    )
    (net (code "26") (name "/_AMOD_19") (class "Default")
      (node (ref "C127") (pin "1") (pinfunction "1_1") (pintype "passive"))
      (node (ref "U73") (pin "8") (pinfunction "A_8") (pintype "input"))
      (node (ref "U75") (pin "7") (pinfunction "Y_7") (pintype "output"))
    )
    (net (code "27") (name "/_AMOD_20") (class "Default")
      (node (ref "C134") (pin "1") (pinfunction "1_1") (pintype "passive"))
      (node (ref "U77") (pin "8") (pinfunction "A_8") (pintype "input"))
      (node (ref "U79") (pin "7") (pinfunction "Y_7") (pintype "output"))
    )
    (net (code "28") (name "/_BMOD_5") (class "Default")
      (node (ref "C2") (pin "1") (pinfunction "1_1") (pintype "passive"))
      (node (ref "U1") (pin "7") (pinfunction "B_7") (pintype "input"))
      (node (ref "U3") (pin "3") (pinfunction "Y_3") (pintype "output"))
    )
    (net (code "29") (name "/_BMOD_6") (class "Default")
      (node (ref "C37") (pin "1") (pinfunction "1_1") (pintype "passive"))
      (node (ref "U21") (pin "7") (pinfunction "B_7") (pintype "input"))
      (node (ref "U23") (pin "3") (pinfunction "Y_3") (pintype "output"))
    )
    (net (code "30") (name "/_BMOD_7") (class "Default")
      (node (ref "C44") (pin "1") (pinfunction "1_1") (pintype "passive"))
      (node (ref "U25") (pin "7") (pinfunction "B_7") (pintype "input"))
      (node (ref "U27") (pin "3") (pinfunction "Y_3") (pintype "output"))
    )
    (net (code "31") (name "/_BMOD_8") (class "Default")
      (node (ref "C51") (pin "1") (pinfunction "1_1") (pintype "passive"))
      (node (ref "U29") (pin "7") (pinfunction "B_7") (pintype "input"))
      (node (ref "U31") (pin "3") (pinfunction "Y_3") (pintype "output"))
    )
    (net (code "32") (name "/_BMOD_9") (class "Default")
      (node (ref "C58") (pin "1") (pinfunction "1_1") (pintype "passive"))
      (node (ref "U33") (pin "7") (pinfunction "B_7") (pintype "input"))
      (node (ref "U35") (pin "3") (pinfunction "Y_3") (pintype "output"))
    )
    (net (code "33") (name "/_BMOD_10") (class "Default")
      (node (ref "C65") (pin "1") (pinfunction "1_1") (pintype "passive"))
      (node (ref "U37") (pin "7") (pinfunction "B_7") (pintype "input"))
      (node (ref "U39") (pin "3") (pinfunction "Y_3") (pintype "output"))
    )
    (net (code "34") (name "/_BMOD_11") (class "Default")
      (node (ref "C72") (pin "1") (pinfunction "1_1") (pintype "passive"))
      (node (ref "U41") (pin "7") (pinfunction "B_7") (pintype "input"))
      (node (ref "U43") (pin "3") (pinfunction "Y_3") (pintype "output"))
    )
    (net (code "35") (name "/_BMOD_12") (class "Default")
      (node (ref "C79") (pin "1") (pinfunction "1_1") (pintype "passive"))
      (node (ref "U45") (pin "7") (pinfunction "B_7") (pintype "input"))
      (node (ref "U47") (pin "3") (pinfunction "Y_3") (pintype "output"))
    )
    (net (code "36") (name "/_BMOD_13") (class "Default")
      (node (ref "C86") (pin "1") (pinfunction "1_1") (pintype "passive"))
      (node (ref "U49") (pin "7") (pinfunction "B_7") (pintype "input"))
      (node (ref "U51") (pin "3") (pinfunction "Y_3") (pintype "output"))
    )
    (net (code "37") (name "/_BMOD_14") (class "Default")
      (node (ref "C93") (pin "1") (pinfunction "1_1") (pintype "passive"))
      (node (ref "U53") (pin "7") (pinfunction "B_7") (pintype "input"))
      (node (ref "U55") (pin "3") (pinfunction "Y_3") (pintype "output"))
    )
    (net (code "38") (name "/_BMOD_15") (class "Default")
      (node (ref "C100") (pin "1") (pinfunction "1_1") (pintype "passive"))
      (node (ref "U57") (pin "7") (pinfunction "B_7") (pintype "input"))
      (node (ref "U59") (pin "3") (pinfunction "Y_3") (pintype "output"))
    )
    (net (code "39") (name "/_BMOD_16") (class "Default")
      (node (ref "C107") (pin "1") (pinfunction "1_1") (pintype "passive"))
      (node (ref "U61") (pin "7") (pinfunction "B_7") (pintype "input"))
      (node (ref "U63") (pin "3") (pinfunction "Y_3") (pintype "output"))
    )
    (net (code "40") (name "/_BMOD_17") (class "Default")
      (node (ref "C114") (pin "1") (pinfunction "1_1") (pintype "passive"))
      (node (ref "U65") (pin "7") (pinfunction "B_7") (pintype "input"))
      (node (ref "U67") (pin "3") (pinfunction "Y_3") (pintype "output"))
    )
    (net (code "41") (name "/_BMOD_18") (class "Default")
      (node (ref "C121") (pin "1") (pinfunction "1_1") (pintype "passive"))
      (node (ref "U69") (pin "7") (pinfunction "B_7") (pintype "input"))
      (node (ref "U71") (pin "3") (pinfunction "Y_3") (pintype "output"))
    )
    (net (code "42") (name "/_BMOD_19") (class "Default")
      (node (ref "C128") (pin "1") (pinfunction "1_1") (pintype "passive"))
      (node (ref "U73") (pin "7") (pinfunction "B_7") (pintype "input"))
      (node (ref "U75") (pin "3") (pinfunction "Y_3") (pintype "output"))
    )
    (net (code "43") (name "/_BMOD_20") (class "Default")
      (node (ref "C135") (pin "1") (pinfunction "1_1") (pintype "passive"))
      (node (ref "U77") (pin "7") (pinfunction "B_7") (pintype "input"))
      (node (ref "U79") (pin "3") (pinfunction "Y_3") (pintype "output"))
    )
    (net (code "44") (name "GND") (class "Default")
      (node (ref "C1") (pin "2") (pinfunction "2_2") (pintype "passive"))
      (node (ref "C100") (pin "2") (pinfunction "2_2") (pintype "passive"))
      (node (ref "C101") (pin "2") (pinfunction "2_2") (pintype "passive"))
      (node (ref "C102") (pin "2") (pinfunction "2_2") (pintype "passive"))
      (node (ref "C103") (pin "2") (pinfunction "2_2") (pintype "passive"))
      (node (ref "C104") (pin "2") (pinfunction "2_2") (pintype "passive"))
      (node (ref "C105") (pin "2") (pinfunction "2_2") (pintype "passive"))
      (node (ref "C106") (pin "2") (pinfunction "2_2") (pintype "passive"))
      (node (ref "C107") (pin "2") (pinfunction "2_2") (pintype "passive"))
      (node (ref "C108") (pin "2") (pinfunction "2_2") (pintype "passive"))
      (node (ref "C109") (pin "2") (pinfunction "2_2") (pintype "passive"))
      (node (ref "C110") (pin "2") (pinfunction "2_2") (pintype "passive"))
      (node (ref "C111") (pin "2") (pinfunction "2_2") (pintype "passive"))
      (node (ref "C112") (pin "2") (pinfunction "2_2") (pintype "passive"))
      (node (ref "C113") (pin "2") (pinfunction "2_2") (pintype "passive"))
      (node (ref "C114") (pin "2") (pinfunction "2_2") (pintype "passive"))
      (node (ref "C115") (pin "2") (pinfunction "2_2") (pintype "passive"))
      (node (ref "C116") (pin "2") (pinfunction "2_2") (pintype "passive"))
      (node (ref "C117") (pin "2") (pinfunction "2_2") (pintype "passive"))
      (node (ref "C118") (pin "2") (pinfunction "2_2") (pintype "passive"))
      (node (ref "C119") (pin "2") (pinfunction "2_2") (pintype "passive"))
      (node (ref "C120") (pin "2") (pinfunction "2_2") (pintype "passive"))
      (node (ref "C121") (pin "2") (pinfunction "2_2") (pintype "passive"))
      (node (ref "C122") (pin "2") (pinfunction "2_2") (pintype "passive"))
      (node (ref "C123") (pin "2") (pinfunction "2_2") (pintype "passive"))
      (node (ref "C124") (pin "2") (pinfunction "2_2") (pintype "passive"))
      (node (ref "C125") (pin "2") (pinfunction "2_2") (pintype "passive"))
      (node (ref "C126") (pin "2") (pinfunction "2_2") (pintype "passive"))
      (node (ref "C127") (pin "2") (pinfunction "2_2") (pintype "passive"))
      (node (ref "C128") (pin "2") (pinfunction "2_2") (pintype "passive"))
      (node (ref "C129") (pin "2") (pinfunction "2_2") (pintype "passive"))
      (node (ref "C130") (pin "2") (pinfunction "2_2") (pintype "passive"))
      (node (ref "C131") (pin "2") (pinfunction "2_2") (pintype "passive"))
      (node (ref "C132") (pin "2") (pinfunction "2_2") (pintype "passive"))
      (node (ref "C133") (pin "2") (pinfunction "2_2") (pintype "passive"))
      (node (ref "C134") (pin "2") (pinfunction "2_2") (pintype "passive"))
      (node (ref "C135") (pin "2") (pinfunction "2_2") (pintype "passive"))
      (node (ref "C136") (pin "2") (pinfunction "2_2") (pintype "passive"))
      (node (ref "C137") (pin "2") (pinfunction "2_2") (pintype "passive"))
      (node (ref "C138") (pin "2") (pinfunction "2_2") (pintype "passive"))
      (node (ref "C139") (pin "2") (pinfunction "2_2") (pintype "passive"))
      (node (ref "C140") (pin "2") (pinfunction "2_2") (pintype "passive"))
      (node (ref "C2") (pin "2") (pinfunction "2_2") (pintype "passive"))
      (node (ref "C3") (pin "2") (pinfunction "2_2") (pintype "passive"))
      (node (ref "C36") (pin "2") (pinfunction "2_2") (pintype "passive"))
      (node (ref "C37") (pin "2") (pinfunction "2_2") (pintype "passive"))
      (node (ref "C38") (pin "2") (pinfunction "2_2") (pintype "passive"))
      (node (ref "C39") (pin "2") (pinfunction "2_2") (pintype "passive"))
      (node (ref "C4") (pin "2") (pinfunction "2_2") (pintype "passive"))
      (node (ref "C40") (pin "2") (pinfunction "2_2") (pintype "passive"))
      (node (ref "C41") (pin "2") (pinfunction "2_2") (pintype "passive"))
      (node (ref "C42") (pin "2") (pinfunction "2_2") (pintype "passive"))
      (node (ref "C43") (pin "2") (pinfunction "2_2") (pintype "passive"))
      (node (ref "C44") (pin "2") (pinfunction "2_2") (pintype "passive"))
      (node (ref "C45") (pin "2") (pinfunction "2_2") (pintype "passive"))
      (node (ref "C46") (pin "2") (pinfunction "2_2") (pintype "passive"))
      (node (ref "C47") (pin "2") (pinfunction "2_2") (pintype "passive"))
      (node (ref "C48") (pin "2") (pinfunction "2_2") (pintype "passive"))
      (node (ref "C49") (pin "2") (pinfunction "2_2") (pintype "passive"))
      (node (ref "C5") (pin "2") (pinfunction "2_2") (pintype "passive"))
      (node (ref "C50") (pin "2") (pinfunction "2_2") (pintype "passive"))
      (node (ref "C51") (pin "2") (pinfunction "2_2") (pintype "passive"))
      (node (ref "C52") (pin "2") (pinfunction "2_2") (pintype "passive"))
      (node (ref "C53") (pin "2") (pinfunction "2_2") (pintype "passive"))
      (node (ref "C54") (pin "2") (pinfunction "2_2") (pintype "passive"))
      (node (ref "C55") (pin "2") (pinfunction "2_2") (pintype "passive"))
      (node (ref "C56") (pin "2") (pinfunction "2_2") (pintype "passive"))
      (node (ref "C57") (pin "2") (pinfunction "2_2") (pintype "passive"))
      (node (ref "C58") (pin "2") (pinfunction "2_2") (pintype "passive"))
      (node (ref "C59") (pin "2") (pinfunction "2_2") (pintype "passive"))
      (node (ref "C6") (pin "2") (pinfunction "2_2") (pintype "passive"))
      (node (ref "C60") (pin "2") (pinfunction "2_2") (pintype "passive"))
      (node (ref "C61") (pin "2") (pinfunction "2_2") (pintype "passive"))
      (node (ref "C62") (pin "2") (pinfunction "2_2") (pintype "passive"))
      (node (ref "C63") (pin "2") (pinfunction "2_2") (pintype "passive"))
      (node (ref "C64") (pin "2") (pinfunction "2_2") (pintype "passive"))
      (node (ref "C65") (pin "2") (pinfunction "2_2") (pintype "passive"))
      (node (ref "C66") (pin "2") (pinfunction "2_2") (pintype "passive"))
      (node (ref "C67") (pin "2") (pinfunction "2_2") (pintype "passive"))
      (node (ref "C68") (pin "2") (pinfunction "2_2") (pintype "passive"))
      (node (ref "C69") (pin "2") (pinfunction "2_2") (pintype "passive"))
      (node (ref "C7") (pin "2") (pinfunction "2_2") (pintype "passive"))
      (node (ref "C70") (pin "2") (pinfunction "2_2") (pintype "passive"))
      (node (ref "C71") (pin "2") (pinfunction "2_2") (pintype "passive"))
      (node (ref "C72") (pin "2") (pinfunction "2_2") (pintype "passive"))
      (node (ref "C73") (pin "2") (pinfunction "2_2") (pintype "passive"))
      (node (ref "C74") (pin "2") (pinfunction "2_2") (pintype "passive"))
      (node (ref "C75") (pin "2") (pinfunction "2_2") (pintype "passive"))
      (node (ref "C76") (pin "2") (pinfunction "2_2") (pintype "passive"))
      (node (ref "C77") (pin "2") (pinfunction "2_2") (pintype "passive"))
      (node (ref "C78") (pin "2") (pinfunction "2_2") (pintype "passive"))
      (node (ref "C79") (pin "2") (pinfunction "2_2") (pintype "passive"))
      (node (ref "C80") (pin "2") (pinfunction "2_2") (pintype "passive"))
      (node (ref "C81") (pin "2") (pinfunction "2_2") (pintype "passive"))
      (node (ref "C82") (pin "2") (pinfunction "2_2") (pintype "passive"))
      (node (ref "C83") (pin "2") (pinfunction "2_2") (pintype "passive"))
      (node (ref "C84") (pin "2") (pinfunction "2_2") (pintype "passive"))
      (node (ref "C85") (pin "2") (pinfunction "2_2") (pintype "passive"))
      (node (ref "C86") (pin "2") (pinfunction "2_2") (pintype "passive"))
      (node (ref "C87") (pin "2") (pinfunction "2_2") (pintype "passive"))
      (node (ref "C88") (pin "2") (pinfunction "2_2") (pintype "passive"))
      (node (ref "C89") (pin "2") (pinfunction "2_2") (pintype "passive"))
      (node (ref "C90") (pin "2") (pinfunction "2_2") (pintype "passive"))
      (node (ref "C91") (pin "2") (pinfunction "2_2") (pintype "passive"))
      (node (ref "C92") (pin "2") (pinfunction "2_2") (pintype "passive"))
      (node (ref "C93") (pin "2") (pinfunction "2_2") (pintype "passive"))
      (node (ref "C94") (pin "2") (pinfunction "2_2") (pintype "passive"))
      (node (ref "C95") (pin "2") (pinfunction "2_2") (pintype "passive"))
      (node (ref "C96") (pin "2") (pinfunction "2_2") (pintype "passive"))
      (node (ref "C97") (pin "2") (pinfunction "2_2") (pintype "passive"))
      (node (ref "C98") (pin "2") (pinfunction "2_2") (pintype "passive"))
      (node (ref "C99") (pin "2") (pinfunction "2_2") (pintype "passive"))
      (node (ref "U1") (pin "10") (pinfunction "GND_10") (pintype "power_in"))
      (node (ref "U1") (pin "11") (pinfunction "GND_11") (pintype "power_in"))
      (node (ref "U1") (pin "13") (pinfunction "GND_13") (pintype "power_in"))
      (node (ref "U1") (pin "14") (pinfunction "GND_14") (pintype "power_in"))
      (node (ref "U1") (pin "16") (pinfunction "GND_16") (pintype "power_in"))
      (node (ref "U1") (pin "2") (pinfunction "GND_2") (pintype "power_in"))
      (node (ref "U1") (pin "3") (pinfunction "GND_3") (pintype "power_in"))
      (node (ref "U1") (pin "5") (pinfunction "GND_5") (pintype "power_in"))
      (node (ref "U1") (pin "PAD") (pinfunction "GND_PAD") (pintype "power_in"))
      (node (ref "U2") (pin "3") (pinfunction "GND_3") (pintype "power_in"))
      (node (ref "U21") (pin "10") (pinfunction "GND_10") (pintype "power_in"))
      (node (ref "U21") (pin "11") (pinfunction "GND_11") (pintype "power_in"))
      (node (ref "U21") (pin "13") (pinfunction "GND_13") (pintype "power_in"))
      (node (ref "U21") (pin "14") (pinfunction "GND_14") (pintype "power_in"))
      (node (ref "U21") (pin "16") (pinfunction "GND_16") (pintype "power_in"))
      (node (ref "U21") (pin "2") (pinfunction "GND_2") (pintype "power_in"))
      (node (ref "U21") (pin "3") (pinfunction "GND_3") (pintype "power_in"))
      (node (ref "U21") (pin "5") (pinfunction "GND_5") (pintype "power_in"))
      (node (ref "U21") (pin "PAD") (pinfunction "GND_PAD") (pintype "power_in"))
      (node (ref "U22") (pin "3") (pinfunction "GND_3") (pintype "power_in"))
      (node (ref "U23") (pin "4") (pinfunction "GND_4") (pintype "power_in"))
      (node (ref "U24") (pin "4") (pinfunction "GND_4") (pintype "power_in"))
      (node (ref "U25") (pin "10") (pinfunction "GND_10") (pintype "power_in"))
      (node (ref "U25") (pin "11") (pinfunction "GND_11") (pintype "power_in"))
      (node (ref "U25") (pin "13") (pinfunction "GND_13") (pintype "power_in"))
      (node (ref "U25") (pin "14") (pinfunction "GND_14") (pintype "power_in"))
      (node (ref "U25") (pin "16") (pinfunction "GND_16") (pintype "power_in"))
      (node (ref "U25") (pin "2") (pinfunction "GND_2") (pintype "power_in"))
      (node (ref "U25") (pin "3") (pinfunction "GND_3") (pintype "power_in"))
      (node (ref "U25") (pin "5") (pinfunction "GND_5") (pintype "power_in"))
      (node (ref "U25") (pin "PAD") (pinfunction "GND_PAD") (pintype "power_in"))
      (node (ref "U26") (pin "3") (pinfunction "GND_3") (pintype "power_in"))
      (node (ref "U27") (pin "4") (pinfunction "GND_4") (pintype "power_in"))
      (node (ref "U28") (pin "4") (pinfunction "GND_4") (pintype "power_in"))
      (node (ref "U29") (pin "10") (pinfunction "GND_10") (pintype "power_in"))
      (node (ref "U29") (pin "11") (pinfunction "GND_11") (pintype "power_in"))
      (node (ref "U29") (pin "13") (pinfunction "GND_13") (pintype "power_in"))
      (node (ref "U29") (pin "14") (pinfunction "GND_14") (pintype "power_in"))
      (node (ref "U29") (pin "16") (pinfunction "GND_16") (pintype "power_in"))
      (node (ref "U29") (pin "2") (pinfunction "GND_2") (pintype "power_in"))
      (node (ref "U29") (pin "3") (pinfunction "GND_3") (pintype "power_in"))
      (node (ref "U29") (pin "5") (pinfunction "GND_5") (pintype "power_in"))
      (node (ref "U29") (pin "PAD") (pinfunction "GND_PAD") (pintype "power_in"))
      (node (ref "U3") (pin "4") (pinfunction "GND_4") (pintype "power_in"))
      (node (ref "U30") (pin "3") (pinfunction "GND_3") (pintype "power_in"))
      (node (ref "U31") (pin "4") (pinfunction "GND_4") (pintype "power_in"))
      (node (ref "U32") (pin "4") (pinfunction "GND_4") (pintype "power_in"))
      (node (ref "U33") (pin "10") (pinfunction "GND_10") (pintype "power_in"))
      (node (ref "U33") (pin "11") (pinfunction "GND_11") (pintype "power_in"))
      (node (ref "U33") (pin "13") (pinfunction "GND_13") (pintype "power_in"))
      (node (ref "U33") (pin "14") (pinfunction "GND_14") (pintype "power_in"))
      (node (ref "U33") (pin "16") (pinfunction "GND_16") (pintype "power_in"))
      (node (ref "U33") (pin "2") (pinfunction "GND_2") (pintype "power_in"))
      (node (ref "U33") (pin "3") (pinfunction "GND_3") (pintype "power_in"))
      (node (ref "U33") (pin "5") (pinfunction "GND_5") (pintype "power_in"))
      (node (ref "U33") (pin "PAD") (pinfunction "GND_PAD") (pintype "power_in"))
      (node (ref "U34") (pin "3") (pinfunction "GND_3") (pintype "power_in"))
      (node (ref "U35") (pin "4") (pinfunction "GND_4") (pintype "power_in"))
      (node (ref "U36") (pin "4") (pinfunction "GND_4") (pintype "power_in"))
      (node (ref "U37") (pin "10") (pinfunction "GND_10") (pintype "power_in"))
      (node (ref "U37") (pin "11") (pinfunction "GND_11") (pintype "power_in"))
      (node (ref "U37") (pin "13") (pinfunction "GND_13") (pintype "power_in"))
      (node (ref "U37") (pin "14") (pinfunction "GND_14") (pintype "power_in"))
      (node (ref "U37") (pin "16") (pinfunction "GND_16") (pintype "power_in"))
      (node (ref "U37") (pin "2") (pinfunction "GND_2") (pintype "power_in"))
      (node (ref "U37") (pin "3") (pinfunction "GND_3") (pintype "power_in"))
      (node (ref "U37") (pin "5") (pinfunction "GND_5") (pintype "power_in"))
      (node (ref "U37") (pin "PAD") (pinfunction "GND_PAD") (pintype "power_in"))
      (node (ref "U38") (pin "3") (pinfunction "GND_3") (pintype "power_in"))
      (node (ref "U39") (pin "4") (pinfunction "GND_4") (pintype "power_in"))
      (node (ref "U4") (pin "4") (pinfunction "GND_4") (pintype "power_in"))
      (node (ref "U40") (pin "4") (pinfunction "GND_4") (pintype "power_in"))
      (node (ref "U41") (pin "10") (pinfunction "GND_10") (pintype "power_in"))
      (node (ref "U41") (pin "11") (pinfunction "GND_11") (pintype "power_in"))
      (node (ref "U41") (pin "13") (pinfunction "GND_13") (pintype "power_in"))
      (node (ref "U41") (pin "14") (pinfunction "GND_14") (pintype "power_in"))
      (node (ref "U41") (pin "16") (pinfunction "GND_16") (pintype "power_in"))
      (node (ref "U41") (pin "2") (pinfunction "GND_2") (pintype "power_in"))
      (node (ref "U41") (pin "3") (pinfunction "GND_3") (pintype "power_in"))
      (node (ref "U41") (pin "5") (pinfunction "GND_5") (pintype "power_in"))
      (node (ref "U41") (pin "PAD") (pinfunction "GND_PAD") (pintype "power_in"))
      (node (ref "U42") (pin "3") (pinfunction "GND_3") (pintype "power_in"))
      (node (ref "U43") (pin "4") (pinfunction "GND_4") (pintype "power_in"))
      (node (ref "U44") (pin "4") (pinfunction "GND_4") (pintype "power_in"))
      (node (ref "U45") (pin "10") (pinfunction "GND_10") (pintype "power_in"))
      (node (ref "U45") (pin "11") (pinfunction "GND_11") (pintype "power_in"))
      (node (ref "U45") (pin "13") (pinfunction "GND_13") (pintype "power_in"))
      (node (ref "U45") (pin "14") (pinfunction "GND_14") (pintype "power_in"))
      (node (ref "U45") (pin "16") (pinfunction "GND_16") (pintype "power_in"))
      (node (ref "U45") (pin "2") (pinfunction "GND_2") (pintype "power_in"))
      (node (ref "U45") (pin "3") (pinfunction "GND_3") (pintype "power_in"))
      (node (ref "U45") (pin "5") (pinfunction "GND_5") (pintype "power_in"))
      (node (ref "U45") (pin "PAD") (pinfunction "GND_PAD") (pintype "power_in"))
      (node (ref "U46") (pin "3") (pinfunction "GND_3") (pintype "power_in"))
      (node (ref "U47") (pin "4") (pinfunction "GND_4") (pintype "power_in"))
      (node (ref "U48") (pin "4") (pinfunction "GND_4") (pintype "power_in"))
      (node (ref "U49") (pin "10") (pinfunction "GND_10") (pintype "power_in"))
      (node (ref "U49") (pin "11") (pinfunction "GND_11") (pintype "power_in"))
      (node (ref "U49") (pin "13") (pinfunction "GND_13") (pintype "power_in"))
      (node (ref "U49") (pin "14") (pinfunction "GND_14") (pintype "power_in"))
      (node (ref "U49") (pin "16") (pinfunction "GND_16") (pintype "power_in"))
      (node (ref "U49") (pin "2") (pinfunction "GND_2") (pintype "power_in"))
      (node (ref "U49") (pin "3") (pinfunction "GND_3") (pintype "power_in"))
      (node (ref "U49") (pin "5") (pinfunction "GND_5") (pintype "power_in"))
      (node (ref "U49") (pin "PAD") (pinfunction "GND_PAD") (pintype "power_in"))
      (node (ref "U50") (pin "3") (pinfunction "GND_3") (pintype "power_in"))
      (node (ref "U51") (pin "4") (pinfunction "GND_4") (pintype "power_in"))
      (node (ref "U52") (pin "4") (pinfunction "GND_4") (pintype "power_in"))
      (node (ref "U53") (pin "10") (pinfunction "GND_10") (pintype "power_in"))
      (node (ref "U53") (pin "11") (pinfunction "GND_11") (pintype "power_in"))
      (node (ref "U53") (pin "13") (pinfunction "GND_13") (pintype "power_in"))
      (node (ref "U53") (pin "14") (pinfunction "GND_14") (pintype "power_in"))
      (node (ref "U53") (pin "16") (pinfunction "GND_16") (pintype "power_in"))
      (node (ref "U53") (pin "2") (pinfunction "GND_2") (pintype "power_in"))
      (node (ref "U53") (pin "3") (pinfunction "GND_3") (pintype "power_in"))
      (node (ref "U53") (pin "5") (pinfunction "GND_5") (pintype "power_in"))
      (node (ref "U53") (pin "PAD") (pinfunction "GND_PAD") (pintype "power_in"))
      (node (ref "U54") (pin "3") (pinfunction "GND_3") (pintype "power_in"))
      (node (ref "U55") (pin "4") (pinfunction "GND_4") (pintype "power_in"))
      (node (ref "U56") (pin "4") (pinfunction "GND_4") (pintype "power_in"))
      (node (ref "U57") (pin "10") (pinfunction "GND_10") (pintype "power_in"))
      (node (ref "U57") (pin "11") (pinfunction "GND_11") (pintype "power_in"))
      (node (ref "U57") (pin "13") (pinfunction "GND_13") (pintype "power_in"))
      (node (ref "U57") (pin "14") (pinfunction "GND_14") (pintype "power_in"))
      (node (ref "U57") (pin "16") (pinfunction "GND_16") (pintype "power_in"))
      (node (ref "U57") (pin "2") (pinfunction "GND_2") (pintype "power_in"))
      (node (ref "U57") (pin "3") (pinfunction "GND_3") (pintype "power_in"))
      (node (ref "U57") (pin "5") (pinfunction "GND_5") (pintype "power_in"))
      (node (ref "U57") (pin "PAD") (pinfunction "GND_PAD") (pintype "power_in"))
      (node (ref "U58") (pin "3") (pinfunction "GND_3") (pintype "power_in"))
      (node (ref "U59") (pin "4") (pinfunction "GND_4") (pintype "power_in"))
      (node (ref "U60") (pin "4") (pinfunction "GND_4") (pintype "power_in"))
      (node (ref "U61") (pin "10") (pinfunction "GND_10") (pintype "power_in"))
      (node (ref "U61") (pin "11") (pinfunction "GND_11") (pintype "power_in"))
      (node (ref "U61") (pin "13") (pinfunction "GND_13") (pintype "power_in"))
      (node (ref "U61") (pin "14") (pinfunction "GND_14") (pintype "power_in"))
      (node (ref "U61") (pin "16") (pinfunction "GND_16") (pintype "power_in"))
      (node (ref "U61") (pin "2") (pinfunction "GND_2") (pintype "power_in"))
      (node (ref "U61") (pin "3") (pinfunction "GND_3") (pintype "power_in"))
      (node (ref "U61") (pin "5") (pinfunction "GND_5") (pintype "power_in"))
      (node (ref "U61") (pin "PAD") (pinfunction "GND_PAD") (pintype "power_in"))
      (node (ref "U62") (pin "3") (pinfunction "GND_3") (pintype "power_in"))
      (node (ref "U63") (pin "4") (pinfunction "GND_4") (pintype "power_in"))
      (node (ref "U64") (pin "4") (pinfunction "GND_4") (pintype "power_in"))
      (node (ref "U65") (pin "10") (pinfunction "GND_10") (pintype "power_in"))
      (node (ref "U65") (pin "11") (pinfunction "GND_11") (pintype "power_in"))
      (node (ref "U65") (pin "13") (pinfunction "GND_13") (pintype "power_in"))
      (node (ref "U65") (pin "14") (pinfunction "GND_14") (pintype "power_in"))
      (node (ref "U65") (pin "16") (pinfunction "GND_16") (pintype "power_in"))
      (node (ref "U65") (pin "2") (pinfunction "GND_2") (pintype "power_in"))
      (node (ref "U65") (pin "3") (pinfunction "GND_3") (pintype "power_in"))
      (node (ref "U65") (pin "5") (pinfunction "GND_5") (pintype "power_in"))
      (node (ref "U65") (pin "PAD") (pinfunction "GND_PAD") (pintype "power_in"))
      (node (ref "U66") (pin "3") (pinfunction "GND_3") (pintype "power_in"))
      (node (ref "U67") (pin "4") (pinfunction "GND_4") (pintype "power_in"))
      (node (ref "U68") (pin "4") (pinfunction "GND_4") (pintype "power_in"))
      (node (ref "U69") (pin "10") (pinfunction "GND_10") (pintype "power_in"))
      (node (ref "U69") (pin "11") (pinfunction "GND_11") (pintype "power_in"))
      (node (ref "U69") (pin "13") (pinfunction "GND_13") (pintype "power_in"))
      (node (ref "U69") (pin "14") (pinfunction "GND_14") (pintype "power_in"))
      (node (ref "U69") (pin "16") (pinfunction "GND_16") (pintype "power_in"))
      (node (ref "U69") (pin "2") (pinfunction "GND_2") (pintype "power_in"))
      (node (ref "U69") (pin "3") (pinfunction "GND_3") (pintype "power_in"))
      (node (ref "U69") (pin "5") (pinfunction "GND_5") (pintype "power_in"))
      (node (ref "U69") (pin "PAD") (pinfunction "GND_PAD") (pintype "power_in"))
      (node (ref "U70") (pin "3") (pinfunction "GND_3") (pintype "power_in"))
      (node (ref "U71") (pin "4") (pinfunction "GND_4") (pintype "power_in"))
      (node (ref "U72") (pin "4") (pinfunction "GND_4") (pintype "power_in"))
      (node (ref "U73") (pin "10") (pinfunction "GND_10") (pintype "power_in"))
      (node (ref "U73") (pin "11") (pinfunction "GND_11") (pintype "power_in"))
      (node (ref "U73") (pin "13") (pinfunction "GND_13") (pintype "power_in"))
      (node (ref "U73") (pin "14") (pinfunction "GND_14") (pintype "power_in"))
      (node (ref "U73") (pin "16") (pinfunction "GND_16") (pintype "power_in"))
      (node (ref "U73") (pin "2") (pinfunction "GND_2") (pintype "power_in"))
      (node (ref "U73") (pin "3") (pinfunction "GND_3") (pintype "power_in"))
      (node (ref "U73") (pin "5") (pinfunction "GND_5") (pintype "power_in"))
      (node (ref "U73") (pin "PAD") (pinfunction "GND_PAD") (pintype "power_in"))
      (node (ref "U74") (pin "3") (pinfunction "GND_3") (pintype "power_in"))
      (node (ref "U75") (pin "4") (pinfunction "GND_4") (pintype "power_in"))
      (node (ref "U76") (pin "4") (pinfunction "GND_4") (pintype "power_in"))
      (node (ref "U77") (pin "10") (pinfunction "GND_10") (pintype "power_in"))
      (node (ref "U77") (pin "11") (pinfunction "GND_11") (pintype "power_in"))
      (node (ref "U77") (pin "13") (pinfunction "GND_13") (pintype "power_in"))
      (node (ref "U77") (pin "14") (pinfunction "GND_14") (pintype "power_in"))
      (node (ref "U77") (pin "16") (pinfunction "GND_16") (pintype "power_in"))
      (node (ref "U77") (pin "2") (pinfunction "GND_2") (pintype "power_in"))
      (node (ref "U77") (pin "3") (pinfunction "GND_3") (pintype "power_in"))
      (node (ref "U77") (pin "5") (pinfunction "GND_5") (pintype "power_in"))
      (node (ref "U77") (pin "PAD") (pinfunction "GND_PAD") (pintype "power_in"))
      (node (ref "U78") (pin "3") (pinfunction "GND_3") (pintype "power_in"))
      (node (ref "U79") (pin "4") (pinfunction "GND_4") (pintype "power_in"))
      (node (ref "U80") (pin "4") (pinfunction "GND_4") (pintype "power_in"))
    )
    (net (code "45") (name "Net-(U1-RFC)") (class "Default")
      (node (ref "ANT1") (pin "FEED") (pinfunction "FEED_FEED") (pintype "bidirectional"))
      (node (ref "U1") (pin "15") (pinfunction "RFC_15") (pintype "passive"))
    )
    (net (code "46") (name "Net-(U2-Y)") (class "Default")
      (node (ref "U2") (pin "4") (pinfunction "Y_4") (pintype "output"))
      (node (ref "U4") (pin "1") (pinfunction "CP_1") (pintype "input"))
      (node (ref "U4") (pin "5") (pinfunction "CP_5") (pintype "input"))
    )
    (net (code "47") (name "Net-(U3-A-Pad1)") (class "Default")
      (node (ref "U3") (pin "1") (pinfunction "A_1") (pintype "input"))
      (node (ref "U4") (pin "3") (pinfunction "Q_3") (pintype "output"))
    )
    (net (code "48") (name "Net-(U3-A-Pad5)") (class "Default")
      (node (ref "U3") (pin "5") (pinfunction "A_5") (pintype "input"))
      (node (ref "U4") (pin "7") (pinfunction "Q_7") (pintype "output"))
    )
    (net (code "49") (name "Net-(U21-RFC)") (class "Default")
      (node (ref "ANT6") (pin "FEED") (pinfunction "FEED_FEED") (pintype "bidirectional"))
      (node (ref "U21") (pin "15") (pinfunction "RFC_15") (pintype "passive"))
    )
    (net (code "50") (name "Net-(U22-Y)") (class "Default")
      (node (ref "U22") (pin "4") (pinfunction "Y_4") (pintype "output"))
      (node (ref "U24") (pin "1") (pinfunction "CP_1") (pintype "input"))
      (node (ref "U24") (pin "5") (pinfunction "CP_5") (pintype "input"))
    )
    (net (code "51") (name "Net-(U23-A-Pad1)") (class "Default")
      (node (ref "U23") (pin "1") (pinfunction "A_1") (pintype "input"))
      (node (ref "U24") (pin "3") (pinfunction "Q_3") (pintype "output"))
    )
    (net (code "52") (name "Net-(U23-A-Pad5)") (class "Default")
      (node (ref "U23") (pin "5") (pinfunction "A_5") (pintype "input"))
      (node (ref "U24") (pin "7") (pinfunction "Q_7") (pintype "output"))
    )
    (net (code "53") (name "Net-(U25-RFC)") (class "Default")
      (node (ref "ANT7") (pin "FEED") (pinfunction "FEED_FEED") (pintype "bidirectional"))
      (node (ref "U25") (pin "15") (pinfunction "RFC_15") (pintype "passive"))
    )
    (net (code "54") (name "Net-(U26-Y)") (class "Default")
      (node (ref "U26") (pin "4") (pinfunction "Y_4") (pintype "output"))
      (node (ref "U28") (pin "1") (pinfunction "CP_1") (pintype "input"))
      (node (ref "U28") (pin "5") (pinfunction "CP_5") (pintype "input"))
    )
    (net (code "55") (name "Net-(U27-A-Pad1)") (class "Default")
      (node (ref "U27") (pin "1") (pinfunction "A_1") (pintype "input"))
      (node (ref "U28") (pin "3") (pinfunction "Q_3") (pintype "output"))
    )
    (net (code "56") (name "Net-(U27-A-Pad5)") (class "Default")
      (node (ref "U27") (pin "5") (pinfunction "A_5") (pintype "input"))
      (node (ref "U28") (pin "7") (pinfunction "Q_7") (pintype "output"))
    )
    (net (code "57") (name "Net-(U29-RFC)") (class "Default")
      (node (ref "ANT8") (pin "FEED") (pinfunction "FEED_FEED") (pintype "bidirectional"))
      (node (ref "U29") (pin "15") (pinfunction "RFC_15") (pintype "passive"))
    )
    (net (code "58") (name "Net-(U30-Y)") (class "Default")
      (node (ref "U30") (pin "4") (pinfunction "Y_4") (pintype "output"))
      (node (ref "U32") (pin "1") (pinfunction "CP_1") (pintype "input"))
      (node (ref "U32") (pin "5") (pinfunction "CP_5") (pintype "input"))
    )
    (net (code "59") (name "Net-(U31-A-Pad1)") (class "Default")
      (node (ref "U31") (pin "1") (pinfunction "A_1") (pintype "input"))
      (node (ref "U32") (pin "3") (pinfunction "Q_3") (pintype "output"))
    )
    (net (code "60") (name "Net-(U31-A-Pad5)") (class "Default")
      (node (ref "U31") (pin "5") (pinfunction "A_5") (pintype "input"))
      (node (ref "U32") (pin "7") (pinfunction "Q_7") (pintype "output"))
    )
    (net (code "61") (name "Net-(U33-RFC)") (class "Default")
      (node (ref "ANT9") (pin "FEED") (pinfunction "FEED_FEED") (pintype "bidirectional"))
      (node (ref "U33") (pin "15") (pinfunction "RFC_15") (pintype "passive"))
    )
    (net (code "62") (name "Net-(U34-Y)") (class "Default")
      (node (ref "U34") (pin "4") (pinfunction "Y_4") (pintype "output"))
      (node (ref "U36") (pin "1") (pinfunction "CP_1") (pintype "input"))
      (node (ref "U36") (pin "5") (pinfunction "CP_5") (pintype "input"))
    )
    (net (code "63") (name "Net-(U35-A-Pad1)") (class "Default")
      (node (ref "U35") (pin "1") (pinfunction "A_1") (pintype "input"))
      (node (ref "U36") (pin "3") (pinfunction "Q_3") (pintype "output"))
    )
    (net (code "64") (name "Net-(U35-A-Pad5)") (class "Default")
      (node (ref "U35") (pin "5") (pinfunction "A_5") (pintype "input"))
      (node (ref "U36") (pin "7") (pinfunction "Q_7") (pintype "output"))
    )
    (net (code "65") (name "Net-(U37-RFC)") (class "Default")
      (node (ref "ANT10") (pin "FEED") (pinfunction "FEED_FEED") (pintype "bidirectional"))
      (node (ref "U37") (pin "15") (pinfunction "RFC_15") (pintype "passive"))
    )
    (net (code "66") (name "Net-(U38-Y)") (class "Default")
      (node (ref "U38") (pin "4") (pinfunction "Y_4") (pintype "output"))
      (node (ref "U40") (pin "1") (pinfunction "CP_1") (pintype "input"))
      (node (ref "U40") (pin "5") (pinfunction "CP_5") (pintype "input"))
    )
    (net (code "67") (name "Net-(U39-A-Pad1)") (class "Default")
      (node (ref "U39") (pin "1") (pinfunction "A_1") (pintype "input"))
      (node (ref "U40") (pin "3") (pinfunction "Q_3") (pintype "output"))
    )
    (net (code "68") (name "Net-(U39-A-Pad5)") (class "Default")
      (node (ref "U39") (pin "5") (pinfunction "A_5") (pintype "input"))
      (node (ref "U40") (pin "7") (pinfunction "Q_7") (pintype "output"))
    )
    (net (code "69") (name "Net-(U41-RFC)") (class "Default")
      (node (ref "ANT11") (pin "FEED") (pinfunction "FEED_FEED") (pintype "bidirectional"))
      (node (ref "U41") (pin "15") (pinfunction "RFC_15") (pintype "passive"))
    )
    (net (code "70") (name "Net-(U42-Y)") (class "Default")
      (node (ref "U42") (pin "4") (pinfunction "Y_4") (pintype "output"))
      (node (ref "U44") (pin "1") (pinfunction "CP_1") (pintype "input"))
      (node (ref "U44") (pin "5") (pinfunction "CP_5") (pintype "input"))
    )
    (net (code "71") (name "Net-(U43-A-Pad1)") (class "Default")
      (node (ref "U43") (pin "1") (pinfunction "A_1") (pintype "input"))
      (node (ref "U44") (pin "3") (pinfunction "Q_3") (pintype "output"))
    )
    (net (code "72") (name "Net-(U43-A-Pad5)") (class "Default")
      (node (ref "U43") (pin "5") (pinfunction "A_5") (pintype "input"))
      (node (ref "U44") (pin "7") (pinfunction "Q_7") (pintype "output"))
    )
    (net (code "73") (name "Net-(U45-RFC)") (class "Default")
      (node (ref "ANT12") (pin "FEED") (pinfunction "FEED_FEED") (pintype "bidirectional"))
      (node (ref "U45") (pin "15") (pinfunction "RFC_15") (pintype "passive"))
    )
    (net (code "74") (name "Net-(U46-Y)") (class "Default")
      (node (ref "U46") (pin "4") (pinfunction "Y_4") (pintype "output"))
      (node (ref "U48") (pin "1") (pinfunction "CP_1") (pintype "input"))
      (node (ref "U48") (pin "5") (pinfunction "CP_5") (pintype "input"))
    )
    (net (code "75") (name "Net-(U47-A-Pad1)") (class "Default")
      (node (ref "U47") (pin "1") (pinfunction "A_1") (pintype "input"))
      (node (ref "U48") (pin "3") (pinfunction "Q_3") (pintype "output"))
    )
    (net (code "76") (name "Net-(U47-A-Pad5)") (class "Default")
      (node (ref "U47") (pin "5") (pinfunction "A_5") (pintype "input"))
      (node (ref "U48") (pin "7") (pinfunction "Q_7") (pintype "output"))
    )
    (net (code "77") (name "Net-(U49-RFC)") (class "Default")
      (node (ref "ANT13") (pin "FEED") (pinfunction "FEED_FEED") (pintype "bidirectional"))
      (node (ref "U49") (pin "15") (pinfunction "RFC_15") (pintype "passive"))
    )
    (net (code "78") (name "Net-(U50-Y)") (class "Default")
      (node (ref "U50") (pin "4") (pinfunction "Y_4") (pintype "output"))
      (node (ref "U52") (pin "1") (pinfunction "CP_1") (pintype "input"))
      (node (ref "U52") (pin "5") (pinfunction "CP_5") (pintype "input"))
    )
    (net (code "79") (name "Net-(U51-A-Pad1)") (class "Default")
      (node (ref "U51") (pin "1") (pinfunction "A_1") (pintype "input"))
      (node (ref "U52") (pin "3") (pinfunction "Q_3") (pintype "output"))
    )
    (net (code "80") (name "Net-(U51-A-Pad5)") (class "Default")
      (node (ref "U51") (pin "5") (pinfunction "A_5") (pintype "input"))
      (node (ref "U52") (pin "7") (pinfunction "Q_7") (pintype "output"))
    )
    (net (code "81") (name "Net-(U53-RFC)") (class "Default")
      (node (ref "ANT14") (pin "FEED") (pinfunction "FEED_FEED") (pintype "bidirectional"))
      (node (ref "U53") (pin "15") (pinfunction "RFC_15") (pintype "passive"))
    )
    (net (code "82") (name "Net-(U54-Y)") (class "Default")
      (node (ref "U54") (pin "4") (pinfunction "Y_4") (pintype "output"))
      (node (ref "U56") (pin "1") (pinfunction "CP_1") (pintype "input"))
      (node (ref "U56") (pin "5") (pinfunction "CP_5") (pintype "input"))
    )
    (net (code "83") (name "Net-(U55-A-Pad1)") (class "Default")
      (node (ref "U55") (pin "1") (pinfunction "A_1") (pintype "input"))
      (node (ref "U56") (pin "3") (pinfunction "Q_3") (pintype "output"))
    )
    (net (code "84") (name "Net-(U55-A-Pad5)") (class "Default")
      (node (ref "U55") (pin "5") (pinfunction "A_5") (pintype "input"))
      (node (ref "U56") (pin "7") (pinfunction "Q_7") (pintype "output"))
    )
    (net (code "85") (name "Net-(U57-RFC)") (class "Default")
      (node (ref "ANT15") (pin "FEED") (pinfunction "FEED_FEED") (pintype "bidirectional"))
      (node (ref "U57") (pin "15") (pinfunction "RFC_15") (pintype "passive"))
    )
    (net (code "86") (name "Net-(U58-Y)") (class "Default")
      (node (ref "U58") (pin "4") (pinfunction "Y_4") (pintype "output"))
      (node (ref "U60") (pin "1") (pinfunction "CP_1") (pintype "input"))
      (node (ref "U60") (pin "5") (pinfunction "CP_5") (pintype "input"))
    )
    (net (code "87") (name "Net-(U59-A-Pad1)") (class "Default")
      (node (ref "U59") (pin "1") (pinfunction "A_1") (pintype "input"))
      (node (ref "U60") (pin "3") (pinfunction "Q_3") (pintype "output"))
    )
    (net (code "88") (name "Net-(U59-A-Pad5)") (class "Default")
      (node (ref "U59") (pin "5") (pinfunction "A_5") (pintype "input"))
      (node (ref "U60") (pin "7") (pinfunction "Q_7") (pintype "output"))
    )
    (net (code "89") (name "Net-(U61-RFC)") (class "Default")
      (node (ref "ANT16") (pin "FEED") (pinfunction "FEED_FEED") (pintype "bidirectional"))
      (node (ref "U61") (pin "15") (pinfunction "RFC_15") (pintype "passive"))
    )
    (net (code "90") (name "Net-(U62-Y)") (class "Default")
      (node (ref "U62") (pin "4") (pinfunction "Y_4") (pintype "output"))
      (node (ref "U64") (pin "1") (pinfunction "CP_1") (pintype "input"))
      (node (ref "U64") (pin "5") (pinfunction "CP_5") (pintype "input"))
    )
    (net (code "91") (name "Net-(U63-A-Pad1)") (class "Default")
      (node (ref "U63") (pin "1") (pinfunction "A_1") (pintype "input"))
      (node (ref "U64") (pin "3") (pinfunction "Q_3") (pintype "output"))
    )
    (net (code "92") (name "Net-(U63-A-Pad5)") (class "Default")
      (node (ref "U63") (pin "5") (pinfunction "A_5") (pintype "input"))
      (node (ref "U64") (pin "7") (pinfunction "Q_7") (pintype "output"))
    )
    (net (code "93") (name "Net-(U65-RFC)") (class "Default")
      (node (ref "ANT17") (pin "FEED") (pinfunction "FEED_FEED") (pintype "bidirectional"))
      (node (ref "U65") (pin "15") (pinfunction "RFC_15") (pintype "passive"))
    )
    (net (code "94") (name "Net-(U66-Y)") (class "Default")
      (node (ref "U66") (pin "4") (pinfunction "Y_4") (pintype "output"))
      (node (ref "U68") (pin "1") (pinfunction "CP_1") (pintype "input"))
      (node (ref "U68") (pin "5") (pinfunction "CP_5") (pintype "input"))
    )
    (net (code "95") (name "Net-(U67-A-Pad1)") (class "Default")
      (node (ref "U67") (pin "1") (pinfunction "A_1") (pintype "input"))
      (node (ref "U68") (pin "3") (pinfunction "Q_3") (pintype "output"))
    )
    (net (code "96") (name "Net-(U67-A-Pad5)") (class "Default")
      (node (ref "U67") (pin "5") (pinfunction "A_5") (pintype "input"))
      (node (ref "U68") (pin "7") (pinfunction "Q_7") (pintype "output"))
    )
    (net (code "97") (name "Net-(U69-RFC)") (class "Default")
      (node (ref "ANT18") (pin "FEED") (pinfunction "FEED_FEED") (pintype "bidirectional"))
      (node (ref "U69") (pin "15") (pinfunction "RFC_15") (pintype "passive"))
    )
    (net (code "98") (name "Net-(U70-Y)") (class "Default")
      (node (ref "U70") (pin "4") (pinfunction "Y_4") (pintype "output"))
      (node (ref "U72") (pin "1") (pinfunction "CP_1") (pintype "input"))
      (node (ref "U72") (pin "5") (pinfunction "CP_5") (pintype "input"))
    )
    (net (code "99") (name "Net-(U71-A-Pad1)") (class "Default")
      (node (ref "U71") (pin "1") (pinfunction "A_1") (pintype "input"))
      (node (ref "U72") (pin "3") (pinfunction "Q_3") (pintype "output"))
    )
    (net (code "100") (name "Net-(U71-A-Pad5)") (class "Default")
      (node (ref "U71") (pin "5") (pinfunction "A_5") (pintype "input"))
      (node (ref "U72") (pin "7") (pinfunction "Q_7") (pintype "output"))
    )
    (net (code "101") (name "Net-(U73-RFC)") (class "Default")
      (node (ref "ANT19") (pin "FEED") (pinfunction "FEED_FEED") (pintype "bidirectional"))
      (node (ref "U73") (pin "15") (pinfunction "RFC_15") (pintype "passive"))
    )
    (net (code "102") (name "Net-(U74-Y)") (class "Default")
      (node (ref "U74") (pin "4") (pinfunction "Y_4") (pintype "output"))
      (node (ref "U76") (pin "1") (pinfunction "CP_1") (pintype "input"))
      (node (ref "U76") (pin "5") (pinfunction "CP_5") (pintype "input"))
    )
    (net (code "103") (name "Net-(U75-A-Pad1)") (class "Default")
      (node (ref "U75") (pin "1") (pinfunction "A_1") (pintype "input"))
      (node (ref "U76") (pin "3") (pinfunction "Q_3") (pintype "output"))
    )
    (net (code "104") (name "Net-(U75-A-Pad5)") (class "Default")
      (node (ref "U75") (pin "5") (pinfunction "A_5") (pintype "input"))
      (node (ref "U76") (pin "7") (pinfunction "Q_7") (pintype "output"))
    )
    (net (code "105") (name "Net-(U77-RFC)") (class "Default")
      (node (ref "ANT20") (pin "FEED") (pinfunction "FEED_FEED") (pintype "bidirectional"))
      (node (ref "U77") (pin "15") (pinfunction "RFC_15") (pintype "passive"))
    )
    (net (code "106") (name "Net-(U78-Y)") (class "Default")
      (node (ref "U78") (pin "4") (pinfunction "Y_4") (pintype "output"))
      (node (ref "U80") (pin "1") (pinfunction "CP_1") (pintype "input"))
      (node (ref "U80") (pin "5") (pinfunction "CP_5") (pintype "input"))
    )
    (net (code "107") (name "Net-(U79-A-Pad1)") (class "Default")
      (node (ref "U79") (pin "1") (pinfunction "A_1") (pintype "input"))
      (node (ref "U80") (pin "3") (pinfunction "Q_3") (pintype "output"))
    )
    (net (code "108") (name "Net-(U79-A-Pad5)") (class "Default")
      (node (ref "U79") (pin "5") (pinfunction "A_5") (pintype "input"))
      (node (ref "U80") (pin "7") (pinfunction "Q_7") (pintype "output"))
    )
    (net (code "109") (name "VCC") (class "Default")
      (node (ref "C101") (pin "1") (pinfunction "1_1") (pintype "passive"))
      (node (ref "C102") (pin "1") (pinfunction "1_1") (pintype "passive"))
      (node (ref "C108") (pin "1") (pinfunction "1_1") (pintype "passive"))
      (node (ref "C109") (pin "1") (pinfunction "1_1") (pintype "passive"))
      (node (ref "C115") (pin "1") (pinfunction "1_1") (pintype "passive"))
      (node (ref "C116") (pin "1") (pinfunction "1_1") (pintype "passive"))
      (node (ref "C122") (pin "1") (pinfunction "1_1") (pintype "passive"))
      (node (ref "C123") (pin "1") (pinfunction "1_1") (pintype "passive"))
      (node (ref "C129") (pin "1") (pinfunction "1_1") (pintype "passive"))
      (node (ref "C130") (pin "1") (pinfunction "1_1") (pintype "passive"))
      (node (ref "C136") (pin "1") (pinfunction "1_1") (pintype "passive"))
      (node (ref "C137") (pin "1") (pinfunction "1_1") (pintype "passive"))
      (node (ref "C3") (pin "1") (pinfunction "1_1") (pintype "passive"))
      (node (ref "C38") (pin "1") (pinfunction "1_1") (pintype "passive"))
      (node (ref "C39") (pin "1") (pinfunction "1_1") (pintype "passive"))
      (node (ref "C4") (pin "1") (pinfunction "1_1") (pintype "passive"))
      (node (ref "C45") (pin "1") (pinfunction "1_1") (pintype "passive"))
      (node (ref "C46") (pin "1") (pinfunction "1_1") (pintype "passive"))
      (node (ref "C52") (pin "1") (pinfunction "1_1") (pintype "passive"))
      (node (ref "C53") (pin "1") (pinfunction "1_1") (pintype "passive"))
      (node (ref "C59") (pin "1") (pinfunction "1_1") (pintype "passive"))
      (node (ref "C60") (pin "1") (pinfunction "1_1") (pintype "passive"))
      (node (ref "C66") (pin "1") (pinfunction "1_1") (pintype "passive"))
      (node (ref "C67") (pin "1") (pinfunction "1_1") (pintype "passive"))
      (node (ref "C73") (pin "1") (pinfunction "1_1") (pintype "passive"))
      (node (ref "C74") (pin "1") (pinfunction "1_1") (pintype "passive"))
      (node (ref "C80") (pin "1") (pinfunction "1_1") (pintype "passive"))
      (node (ref "C81") (pin "1") (pinfunction "1_1") (pintype "passive"))
      (node (ref "C87") (pin "1") (pinfunction "1_1") (pintype "passive"))
      (node (ref "C88") (pin "1") (pinfunction "1_1") (pintype "passive"))
      (node (ref "C94") (pin "1") (pinfunction "1_1") (pintype "passive"))
      (node (ref "C95") (pin "1") (pinfunction "1_1") (pintype "passive"))
      (node (ref "U1") (pin "6") (pinfunction "VDD_6") (pintype "power_in"))
      (node (ref "U21") (pin "6") (pinfunction "VDD_6") (pintype "power_in"))
      (node (ref "U25") (pin "6") (pinfunction "VDD_6") (pintype "power_in"))
      (node (ref "U29") (pin "6") (pinfunction "VDD_6") (pintype "power_in"))
      (node (ref "U33") (pin "6") (pinfunction "VDD_6") (pintype "power_in"))
      (node (ref "U37") (pin "6") (pinfunction "VDD_6") (pintype "power_in"))
      (node (ref "U41") (pin "6") (pinfunction "VDD_6") (pintype "power_in"))
      (node (ref "U45") (pin "6") (pinfunction "VDD_6") (pintype "power_in"))
      (node (ref "U49") (pin "6") (pinfunction "VDD_6") (pintype "power_in"))
      (node (ref "U53") (pin "6") (pinfunction "VDD_6") (pintype "power_in"))
      (node (ref "U57") (pin "6") (pinfunction "VDD_6") (pintype "power_in"))
      (node (ref "U61") (pin "6") (pinfunction "VDD_6") (pintype "power_in"))
      (node (ref "U65") (pin "6") (pinfunction "VDD_6") (pintype "power_in"))
      (node (ref "U69") (pin "6") (pinfunction "VDD_6") (pintype "power_in"))
      (node (ref "U73") (pin "6") (pinfunction "VDD_6") (pintype "power_in"))
      (node (ref "U77") (pin "6") (pinfunction "VDD_6") (pintype "power_in"))
    )
    (net (code "110") (name "VCCIO") (class "Default")
      (node (ref "C103") (pin "1") (pinfunction "1_1") (pintype "passive"))
      (node (ref "C104") (pin "1") (pinfunction "1_1") (pintype "passive"))
      (node (ref "C105") (pin "1") (pinfunction "1_1") (pintype "passive"))
      (node (ref "C110") (pin "1") (pinfunction "1_1") (pintype "passive"))
      (node (ref "C111") (pin "1") (pinfunction "1_1") (pintype "passive"))
      (node (ref "C112") (pin "1") (pinfunction "1_1") (pintype "passive"))
      (node (ref "C117") (pin "1") (pinfunction "1_1") (pintype "passive"))
      (node (ref "C118") (pin "1") (pinfunction "1_1") (pintype "passive"))
      (node (ref "C119") (pin "1") (pinfunction "1_1") (pintype "passive"))
      (node (ref "C124") (pin "1") (pinfunction "1_1") (pintype "passive"))
      (node (ref "C125") (pin "1") (pinfunction "1_1") (pintype "passive"))
      (node (ref "C126") (pin "1") (pinfunction "1_1") (pintype "passive"))
      (node (ref "C131") (pin "1") (pinfunction "1_1") (pintype "passive"))
      (node (ref "C132") (pin "1") (pinfunction "1_1") (pintype "passive"))
      (node (ref "C133") (pin "1") (pinfunction "1_1") (pintype "passive"))
      (node (ref "C138") (pin "1") (pinfunction "1_1") (pintype "passive"))
      (node (ref "C139") (pin "1") (pinfunction "1_1") (pintype "passive"))
      (node (ref "C140") (pin "1") (pinfunction "1_1") (pintype "passive"))
      (node (ref "C40") (pin "1") (pinfunction "1_1") (pintype "passive"))
      (node (ref "C41") (pin "1") (pinfunction "1_1") (pintype "passive"))
      (node (ref "C42") (pin "1") (pinfunction "1_1") (pintype "passive"))
      (node (ref "C47") (pin "1") (pinfunction "1_1") (pintype "passive"))
      (node (ref "C48") (pin "1") (pinfunction "1_1") (pintype "passive"))
      (node (ref "C49") (pin "1") (pinfunction "1_1") (pintype "passive"))
      (node (ref "C5") (pin "1") (pinfunction "1_1") (pintype "passive"))
      (node (ref "C54") (pin "1") (pinfunction "1_1") (pintype "passive"))
      (node (ref "C55") (pin "1") (pinfunction "1_1") (pintype "passive"))
      (node (ref "C56") (pin "1") (pinfunction "1_1") (pintype "passive"))
      (node (ref "C6") (pin "1") (pinfunction "1_1") (pintype "passive"))
      (node (ref "C61") (pin "1") (pinfunction "1_1") (pintype "passive"))
      (node (ref "C62") (pin "1") (pinfunction "1_1") (pintype "passive"))
      (node (ref "C63") (pin "1") (pinfunction "1_1") (pintype "passive"))
      (node (ref "C68") (pin "1") (pinfunction "1_1") (pintype "passive"))
      (node (ref "C69") (pin "1") (pinfunction "1_1") (pintype "passive"))
      (node (ref "C7") (pin "1") (pinfunction "1_1") (pintype "passive"))
      (node (ref "C70") (pin "1") (pinfunction "1_1") (pintype "passive"))
      (node (ref "C75") (pin "1") (pinfunction "1_1") (pintype "passive"))
      (node (ref "C76") (pin "1") (pinfunction "1_1") (pintype "passive"))
      (node (ref "C77") (pin "1") (pinfunction "1_1") (pintype "passive"))
      (node (ref "C82") (pin "1") (pinfunction "1_1") (pintype "passive"))
      (node (ref "C83") (pin "1") (pinfunction "1_1") (pintype "passive"))
      (node (ref "C84") (pin "1") (pinfunction "1_1") (pintype "passive"))
      (node (ref "C89") (pin "1") (pinfunction "1_1") (pintype "passive"))
      (node (ref "C90") (pin "1") (pinfunction "1_1") (pintype "passive"))
      (node (ref "C91") (pin "1") (pinfunction "1_1") (pintype "passive"))
      (node (ref "C96") (pin "1") (pinfunction "1_1") (pintype "passive"))
      (node (ref "C97") (pin "1") (pinfunction "1_1") (pintype "passive"))
      (node (ref "C98") (pin "1") (pinfunction "1_1") (pintype "passive"))
      (node (ref "U2") (pin "5") (pinfunction "VCC_5") (pintype "power_in"))
      (node (ref "U22") (pin "5") (pinfunction "VCC_5") (pintype "power_in"))
      (node (ref "U23") (pin "8") (pinfunction "VCC_8") (pintype "power_in"))
      (node (ref "U24") (pin "8") (pinfunction "VCC_8") (pintype "power_in"))
      (node (ref "U26") (pin "5") (pinfunction "VCC_5") (pintype "power_in"))
      (node (ref "U27") (pin "8") (pinfunction "VCC_8") (pintype "power_in"))
      (node (ref "U28") (pin "8") (pinfunction "VCC_8") (pintype "power_in"))
      (node (ref "U3") (pin "8") (pinfunction "VCC_8") (pintype "power_in"))
      (node (ref "U30") (pin "5") (pinfunction "VCC_5") (pintype "power_in"))
      (node (ref "U31") (pin "8") (pinfunction "VCC_8") (pintype "power_in"))
      (node (ref "U32") (pin "8") (pinfunction "VCC_8") (pintype "power_in"))
      (node (ref "U34") (pin "5") (pinfunction "VCC_5") (pintype "power_in"))
      (node (ref "U35") (pin "8") (pinfunction "VCC_8") (pintype "power_in"))
      (node (ref "U36") (pin "8") (pinfunction "VCC_8") (pintype "power_in"))
      (node (ref "U38") (pin "5") (pinfunction "VCC_5") (pintype "power_in"))
      (node (ref "U39") (pin "8") (pinfunction "VCC_8") (pintype "power_in"))
      (node (ref "U4") (pin "8") (pinfunction "VCC_8") (pintype "power_in"))
      (node (ref "U40") (pin "8") (pinfunction "VCC_8") (pintype "power_in"))
      (node (ref "U42") (pin "5") (pinfunction "VCC_5") (pintype "power_in"))
      (node (ref "U43") (pin "8") (pinfunction "VCC_8") (pintype "power_in"))
      (node (ref "U44") (pin "8") (pinfunction "VCC_8") (pintype "power_in"))
      (node (ref "U46") (pin "5") (pinfunction "VCC_5") (pintype "power_in"))
      (node (ref "U47") (pin "8") (pinfunction "VCC_8") (pintype "power_in"))
      (node (ref "U48") (pin "8") (pinfunction "VCC_8") (pintype "power_in"))
      (node (ref "U50") (pin "5") (pinfunction "VCC_5") (pintype "power_in"))
      (node (ref "U51") (pin "8") (pinfunction "VCC_8") (pintype "power_in"))
      (node (ref "U52") (pin "8") (pinfunction "VCC_8") (pintype "power_in"))
      (node (ref "U54") (pin "5") (pinfunction "VCC_5") (pintype "power_in"))
      (node (ref "U55") (pin "8") (pinfunction "VCC_8") (pintype "power_in"))
      (node (ref "U56") (pin "8") (pinfunction "VCC_8") (pintype "power_in"))
      (node (ref "U58") (pin "5") (pinfunction "VCC_5") (pintype "power_in"))
      (node (ref "U59") (pin "8") (pinfunction "VCC_8") (pintype "power_in"))
      (node (ref "U60") (pin "8") (pinfunction "VCC_8") (pintype "power_in"))
      (node (ref "U62") (pin "5") (pinfunction "VCC_5") (pintype "power_in"))
      (node (ref "U63") (pin "8") (pinfunction "VCC_8") (pintype "power_in"))
      (node (ref "U64") (pin "8") (pinfunction "VCC_8") (pintype "power_in"))
      (node (ref "U66") (pin "5") (pinfunction "VCC_5") (pintype "power_in"))
      (node (ref "U67") (pin "8") (pinfunction "VCC_8") (pintype "power_in"))
      (node (ref "U68") (pin "8") (pinfunction "VCC_8") (pintype "power_in"))
      (node (ref "U70") (pin "5") (pinfunction "VCC_5") (pintype "power_in"))
      (node (ref "U71") (pin "8") (pinfunction "VCC_8") (pintype "power_in"))
      (node (ref "U72") (pin "8") (pinfunction "VCC_8") (pintype "power_in"))
      (node (ref "U74") (pin "5") (pinfunction "VCC_5") (pintype "power_in"))
      (node (ref "U75") (pin "8") (pinfunction "VCC_8") (pintype "power_in"))
      (node (ref "U76") (pin "8") (pinfunction "VCC_8") (pintype "power_in"))
      (node (ref "U78") (pin "5") (pinfunction "VCC_5") (pintype "power_in"))
      (node (ref "U79") (pin "8") (pinfunction "VCC_8") (pintype "power_in"))
      (node (ref "U80") (pin "8") (pinfunction "VCC_8") (pintype "power_in"))
    )
    (net (code "111") (name "unconnected-(U1-RF1-Pad12)") (class "Default")
      (node (ref "U1") (pin "12") (pinfunction "RF1_12") (pintype "passive"))
    )
    (net (code "112") (name "unconnected-(U1-RF2-Pad9)") (class "Default")
      (node (ref "U1") (pin "9") (pinfunction "RF2_9") (pintype "passive"))
    )
    (net (code "113") (name "unconnected-(U1-RF3-Pad4)") (class "Default")
      (node (ref "U1") (pin "4") (pinfunction "RF3_4") (pintype "passive"))
    )
    (net (code "114") (name "unconnected-(U1-RF4-Pad1)") (class "Default")
      (node (ref "U1") (pin "1") (pinfunction "RF4_1") (pintype "passive"))
    )
    (net (code "115") (name "unconnected-(U21-RF1-Pad12)") (class "Default")
      (node (ref "U21") (pin "12") (pinfunction "RF1_12") (pintype "passive"))
    )
    (net (code "116") (name "unconnected-(U21-RF2-Pad9)") (class "Default")
      (node (ref "U21") (pin "9") (pinfunction "RF2_9") (pintype "passive"))
    )
    (net (code "117") (name "unconnected-(U21-RF3-Pad4)") (class "Default")
      (node (ref "U21") (pin "4") (pinfunction "RF3_4") (pintype "passive"))
    )
    (net (code "118") (name "unconnected-(U21-RF4-Pad1)") (class "Default")
      (node (ref "U21") (pin "1") (pinfunction "RF4_1") (pintype "passive"))
    )
    (net (code "119") (name "unconnected-(U25-RF1-Pad12)") (class "Default")
      (node (ref "U25") (pin "12") (pinfunction "RF1_12") (pintype "passive"))
    )
    (net (code "120") (name "unconnected-(U25-RF2-Pad9)") (class "Default")
      (node (ref "U25") (pin "9") (pinfunction "RF2_9") (pintype "passive"))
    )
    (net (code "121") (name "unconnected-(U25-RF3-Pad4)") (class "Default")
      (node (ref "U25") (pin "4") (pinfunction "RF3_4") (pintype "passive"))
    )
    (net (code "122") (name "unconnected-(U25-RF4-Pad1)") (class "Default")
      (node (ref "U25") (pin "1") (pinfunction "RF4_1") (pintype "passive"))
    )
    (net (code "123") (name "unconnected-(U29-RF1-Pad12)") (class "Default")
      (node (ref "U29") (pin "12") (pinfunction "RF1_12") (pintype "passive"))
    )
    (net (code "124") (name "unconnected-(U29-RF2-Pad9)") (class "Default")
      (node (ref "U29") (pin "9") (pinfunction "RF2_9") (pintype "passive"))
    )
    (net (code "125") (name "unconnected-(U29-RF3-Pad4)") (class "Default")
      (node (ref "U29") (pin "4") (pinfunction "RF3_4") (pintype "passive"))
    )
    (net (code "126") (name "unconnected-(U29-RF4-Pad1)") (class "Default")
      (node (ref "U29") (pin "1") (pinfunction "RF4_1") (pintype "passive"))
    )
    (net (code "127") (name "unconnected-(U33-RF1-Pad12)") (class "Default")
      (node (ref "U33") (pin "12") (pinfunction "RF1_12") (pintype "passive"))
    )
    (net (code "128") (name "unconnected-(U33-RF2-Pad9)") (class "Default")
      (node (ref "U33") (pin "9") (pinfunction "RF2_9") (pintype "passive"))
    )
    (net (code "129") (name "unconnected-(U33-RF3-Pad4)") (class "Default")
      (node (ref "U33") (pin "4") (pinfunction "RF3_4") (pintype "passive"))
    )
    (net (code "130") (name "unconnected-(U33-RF4-Pad1)") (class "Default")
      (node (ref "U33") (pin "1") (pinfunction "RF4_1") (pintype "passive"))
    )
    (net (code "131") (name "unconnected-(U37-RF1-Pad12)") (class "Default")
      (node (ref "U37") (pin "12") (pinfunction "RF1_12") (pintype "passive"))
    )
    (net (code "132") (name "unconnected-(U37-RF2-Pad9)") (class "Default")
      (node (ref "U37") (pin "9") (pinfunction "RF2_9") (pintype "passive"))
    )
    (net (code "133") (name "unconnected-(U37-RF3-Pad4)") (class "Default")
      (node (ref "U37") (pin "4") (pinfunction "RF3_4") (pintype "passive"))
    )
    (net (code "134") (name "unconnected-(U37-RF4-Pad1)") (class "Default")
      (node (ref "U37") (pin "1") (pinfunction "RF4_1") (pintype "passive"))
    )
    (net (code "135") (name "unconnected-(U41-RF1-Pad12)") (class "Default")
      (node (ref "U41") (pin "12") (pinfunction "RF1_12") (pintype "passive"))
    )
    (net (code "136") (name "unconnected-(U41-RF2-Pad9)") (class "Default")
      (node (ref "U41") (pin "9") (pinfunction "RF2_9") (pintype "passive"))
    )
    (net (code "137") (name "unconnected-(U41-RF3-Pad4)") (class "Default")
      (node (ref "U41") (pin "4") (pinfunction "RF3_4") (pintype "passive"))
    )
    (net (code "138") (name "unconnected-(U41-RF4-Pad1)") (class "Default")
      (node (ref "U41") (pin "1") (pinfunction "RF4_1") (pintype "passive"))
    )
    (net (code "139") (name "unconnected-(U45-RF1-Pad12)") (class "Default")
      (node (ref "U45") (pin "12") (pinfunction "RF1_12") (pintype "passive"))
    )
    (net (code "140") (name "unconnected-(U45-RF2-Pad9)") (class "Default")
      (node (ref "U45") (pin "9") (pinfunction "RF2_9") (pintype "passive"))
    )
    (net (code "141") (name "unconnected-(U45-RF3-Pad4)") (class "Default")
      (node (ref "U45") (pin "4") (pinfunction "RF3_4") (pintype "passive"))
    )
    (net (code "142") (name "unconnected-(U45-RF4-Pad1)") (class "Default")
      (node (ref "U45") (pin "1") (pinfunction "RF4_1") (pintype "passive"))
    )
    (net (code "143") (name "unconnected-(U49-RF1-Pad12)") (class "Default")
      (node (ref "U49") (pin "12") (pinfunction "RF1_12") (pintype "passive"))
    )
    (net (code "144") (name "unconnected-(U49-RF2-Pad9)") (class "Default")
      (node (ref "U49") (pin "9") (pinfunction "RF2_9") (pintype "passive"))
    )
    (net (code "145") (name "unconnected-(U49-RF3-Pad4)") (class "Default")
      (node (ref "U49") (pin "4") (pinfunction "RF3_4") (pintype "passive"))
    )
    (net (code "146") (name "unconnected-(U49-RF4-Pad1)") (class "Default")
      (node (ref "U49") (pin "1") (pinfunction "RF4_1") (pintype "passive"))
    )
    (net (code "147") (name "unconnected-(U53-RF1-Pad12)") (class "Default")
      (node (ref "U53") (pin "12") (pinfunction "RF1_12") (pintype "passive"))
    )
    (net (code "148") (name "unconnected-(U53-RF2-Pad9)") (class "Default")
      (node (ref "U53") (pin "9") (pinfunction "RF2_9") (pintype "passive"))
    )
    (net (code "149") (name "unconnected-(U53-RF3-Pad4)") (class "Default")
      (node (ref "U53") (pin "4") (pinfunction "RF3_4") (pintype "passive"))
    )
    (net (code "150") (name "unconnected-(U53-RF4-Pad1)") (class "Default")
      (node (ref "U53") (pin "1") (pinfunction "RF4_1") (pintype "passive"))
    )
    (net (code "151") (name "unconnected-(U57-RF1-Pad12)") (class "Default")
      (node (ref "U57") (pin "12") (pinfunction "RF1_12") (pintype "passive"))
    )
    (net (code "152") (name "unconnected-(U57-RF2-Pad9)") (class "Default")
      (node (ref "U57") (pin "9") (pinfunction "RF2_9") (pintype "passive"))
    )
    (net (code "153") (name "unconnected-(U57-RF3-Pad4)") (class "Default")
      (node (ref "U57") (pin "4") (pinfunction "RF3_4") (pintype "passive"))
    )
    (net (code "154") (name "unconnected-(U57-RF4-Pad1)") (class "Default")
      (node (ref "U57") (pin "1") (pinfunction "RF4_1") (pintype "passive"))
    )
    (net (code "155") (name "unconnected-(U61-RF1-Pad12)") (class "Default")
      (node (ref "U61") (pin "12") (pinfunction "RF1_12") (pintype "passive"))
    )
    (net (code "156") (name "unconnected-(U61-RF2-Pad9)") (class "Default")
      (node (ref "U61") (pin "9") (pinfunction "RF2_9") (pintype "passive"))
    )
    (net (code "157") (name "unconnected-(U61-RF3-Pad4)") (class "Default")
      (node (ref "U61") (pin "4") (pinfunction "RF3_4") (pintype "passive"))
    )
    (net (code "158") (name "unconnected-(U61-RF4-Pad1)") (class "Default")
      (node (ref "U61") (pin "1") (pinfunction "RF4_1") (pintype "passive"))
    )
    (net (code "159") (name "unconnected-(U65-RF1-Pad12)") (class "Default")
      (node (ref "U65") (pin "12") (pinfunction "RF1_12") (pintype "passive"))
    )
    (net (code "160") (name "unconnected-(U65-RF2-Pad9)") (class "Default")
      (node (ref "U65") (pin "9") (pinfunction "RF2_9") (pintype "passive"))
    )
    (net (code "161") (name "unconnected-(U65-RF3-Pad4)") (class "Default")
      (node (ref "U65") (pin "4") (pinfunction "RF3_4") (pintype "passive"))
    )
    (net (code "162") (name "unconnected-(U65-RF4-Pad1)") (class "Default")
      (node (ref "U65") (pin "1") (pinfunction "RF4_1") (pintype "passive"))
    )
    (net (code "163") (name "unconnected-(U69-RF1-Pad12)") (class "Default")
      (node (ref "U69") (pin "12") (pinfunction "RF1_12") (pintype "passive"))
    )
    (net (code "164") (name "unconnected-(U69-RF2-Pad9)") (class "Default")
      (node (ref "U69") (pin "9") (pinfunction "RF2_9") (pintype "passive"))
    )
    (net (code "165") (name "unconnected-(U69-RF3-Pad4)") (class "Default")
      (node (ref "U69") (pin "4") (pinfunction "RF3_4") (pintype "passive"))
    )
    (net (code "166") (name "unconnected-(U69-RF4-Pad1)") (class "Default")
      (node (ref "U69") (pin "1") (pinfunction "RF4_1") (pintype "passive"))
    )
    (net (code "167") (name "unconnected-(U73-RF1-Pad12)") (class "Default")
      (node (ref "U73") (pin "12") (pinfunction "RF1_12") (pintype "passive"))
    )
    (net (code "168") (name "unconnected-(U73-RF2-Pad9)") (class "Default")
      (node (ref "U73") (pin "9") (pinfunction "RF2_9") (pintype "passive"))
    )
    (net (code "169") (name "unconnected-(U73-RF3-Pad4)") (class "Default")
      (node (ref "U73") (pin "4") (pinfunction "RF3_4") (pintype "passive"))
    )
    (net (code "170") (name "unconnected-(U73-RF4-Pad1)") (class "Default")
      (node (ref "U73") (pin "1") (pinfunction "RF4_1") (pintype "passive"))
    )
    (net (code "171") (name "unconnected-(U77-RF1-Pad12)") (class "Default")
      (node (ref "U77") (pin "12") (pinfunction "RF1_12") (pintype "passive"))
    )
    (net (code "172") (name "unconnected-(U77-RF2-Pad9)") (class "Default")
      (node (ref "U77") (pin "9") (pinfunction "RF2_9") (pintype "passive"))
    )
    (net (code "173") (name "unconnected-(U77-RF3-Pad4)") (class "Default")
      (node (ref "U77") (pin "4") (pinfunction "RF3_4") (pintype "passive"))
    )
    (net (code "174") (name "unconnected-(U77-RF4-Pad1)") (class "Default")
      (node (ref "U77") (pin "1") (pinfunction "RF4_1") (pintype "passive"))
    )
  )
)
